# motor_board_tmc.net
KiCad netlist of a schematic drawn in EAGLE
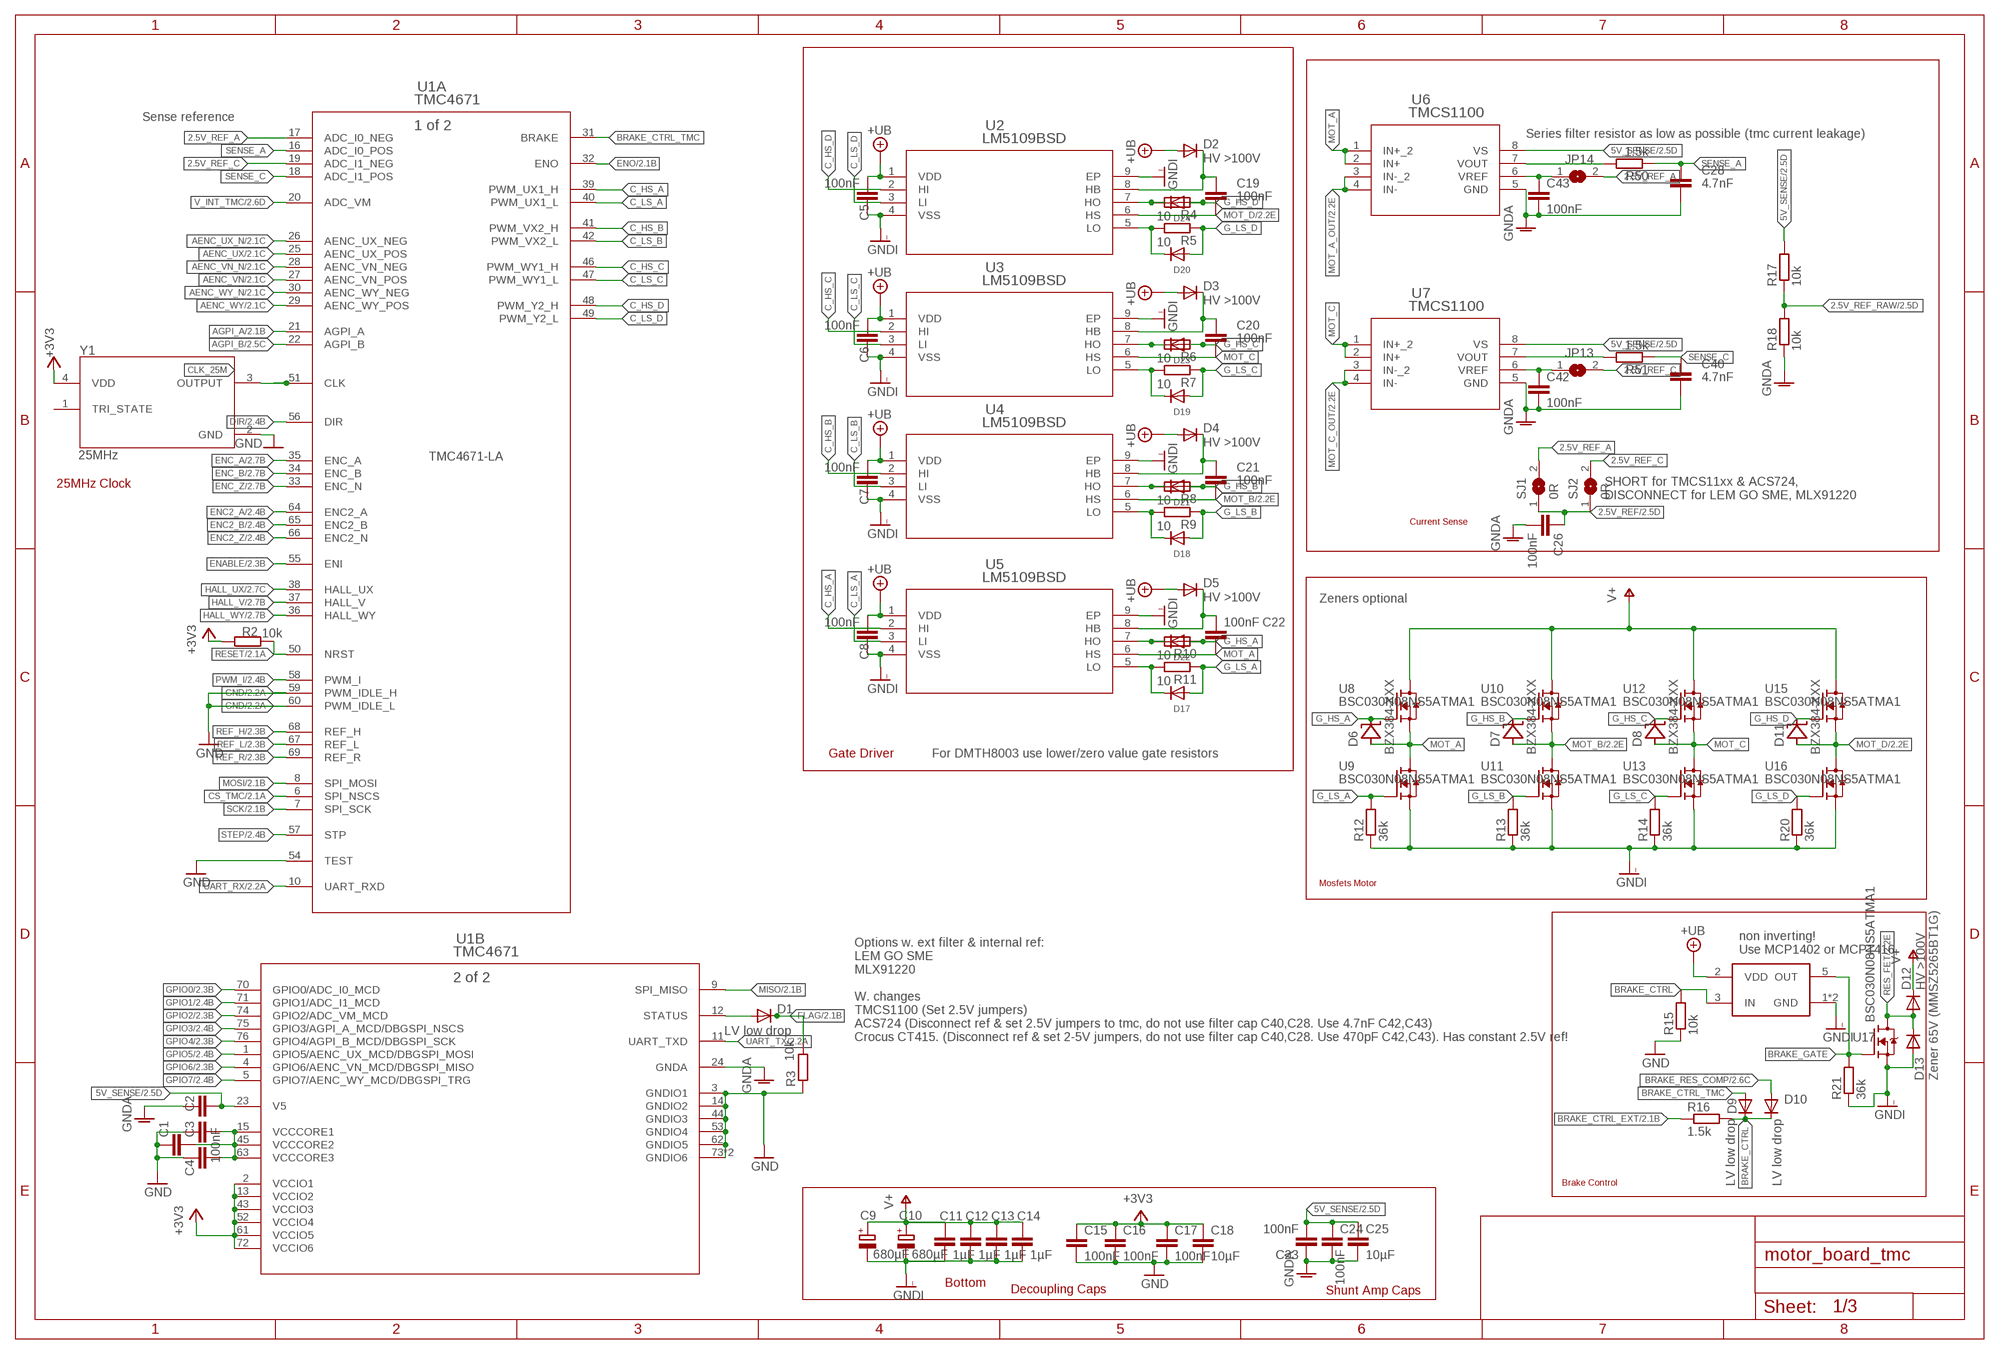
[diagram p0: schematic, sheet 1]
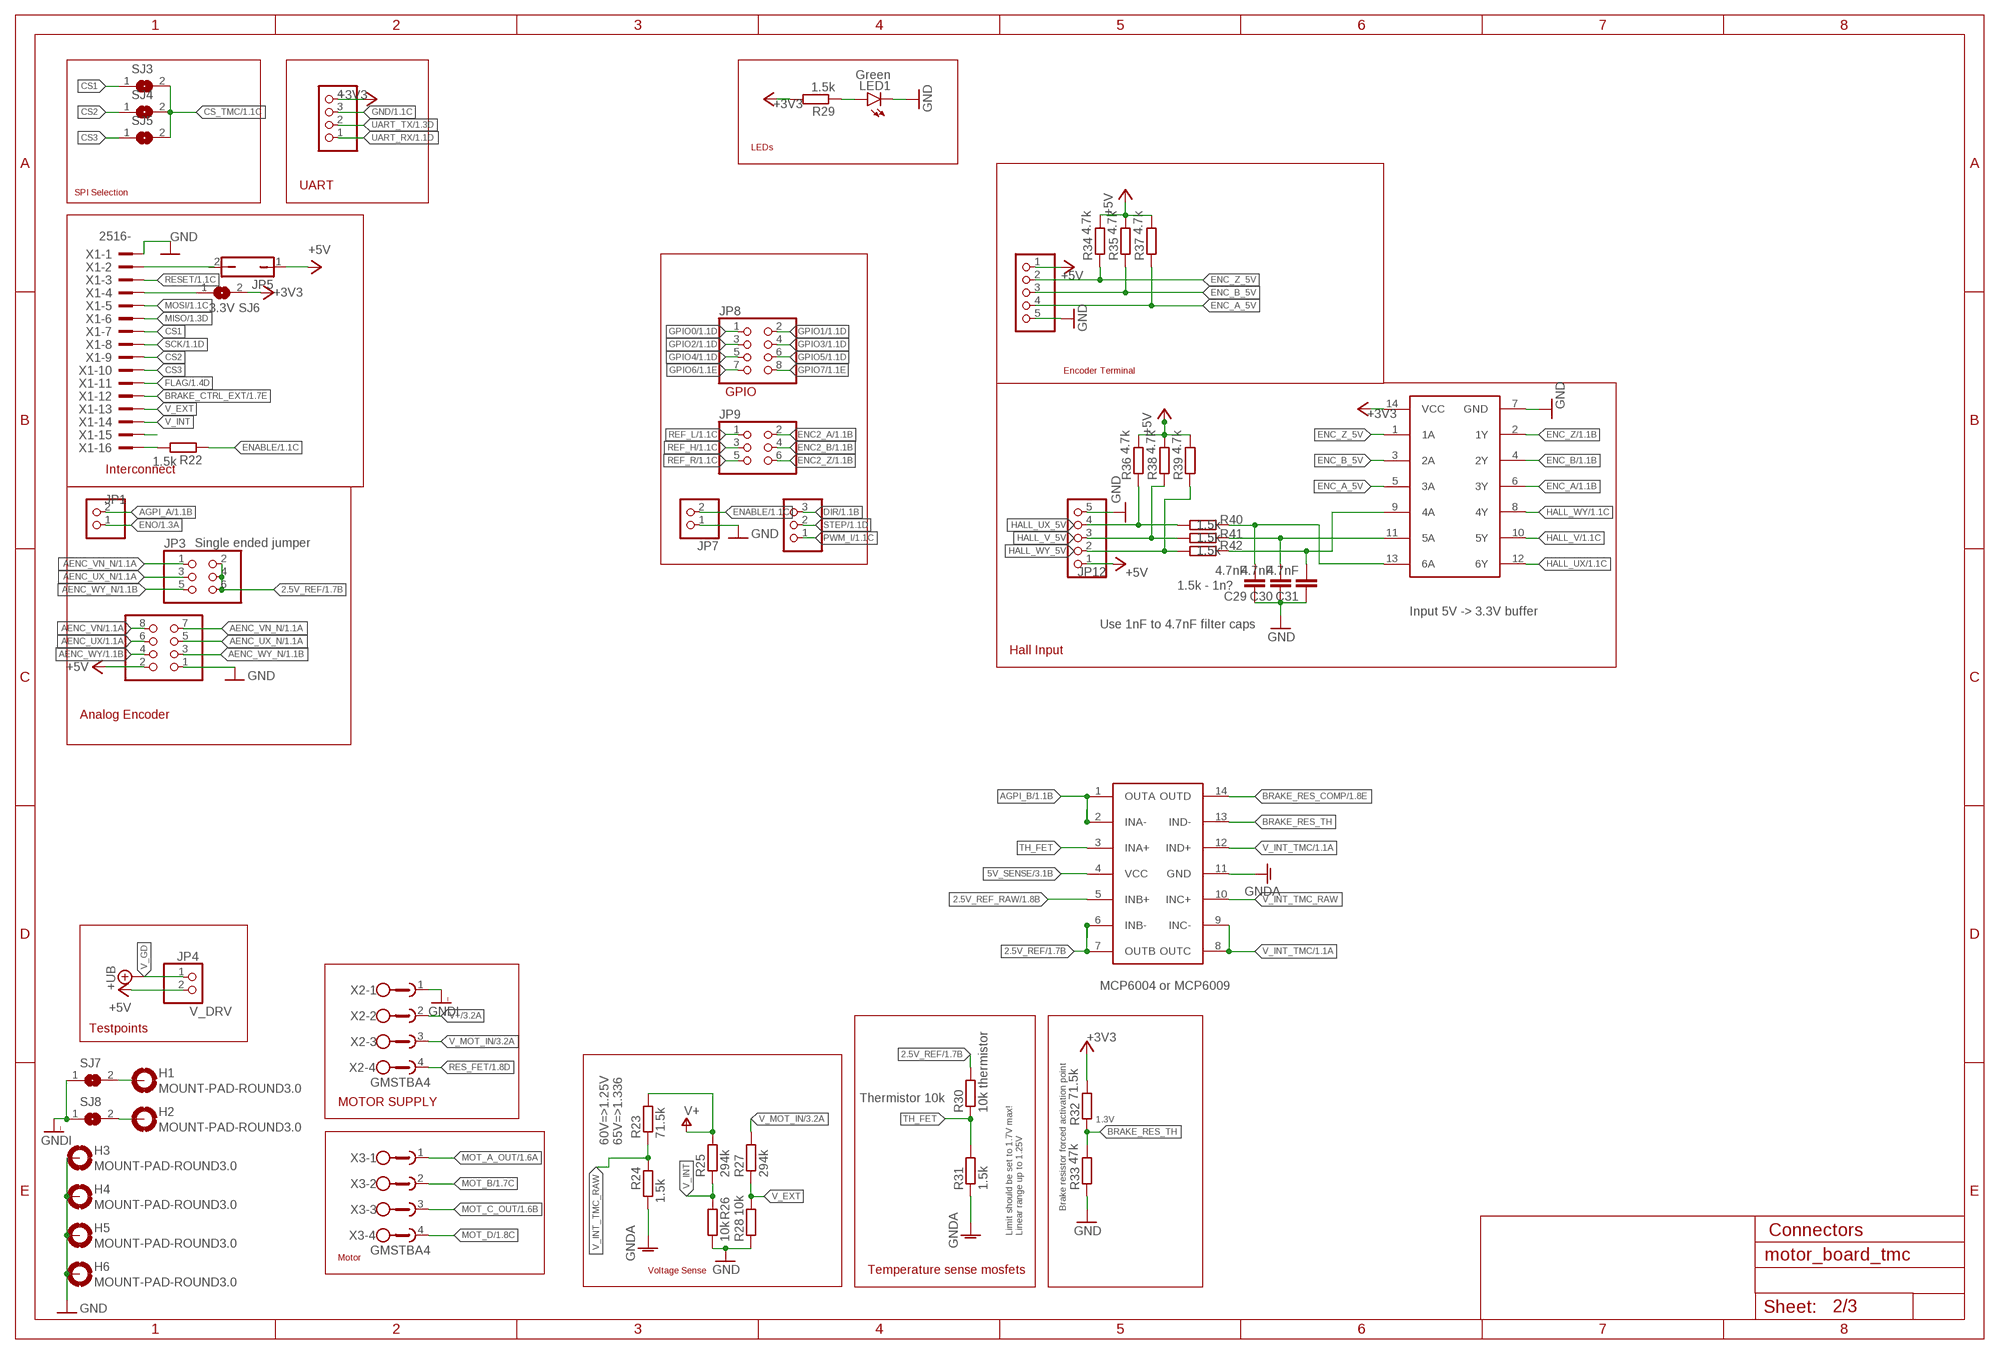
[diagram p1: schematic, sheet 2]
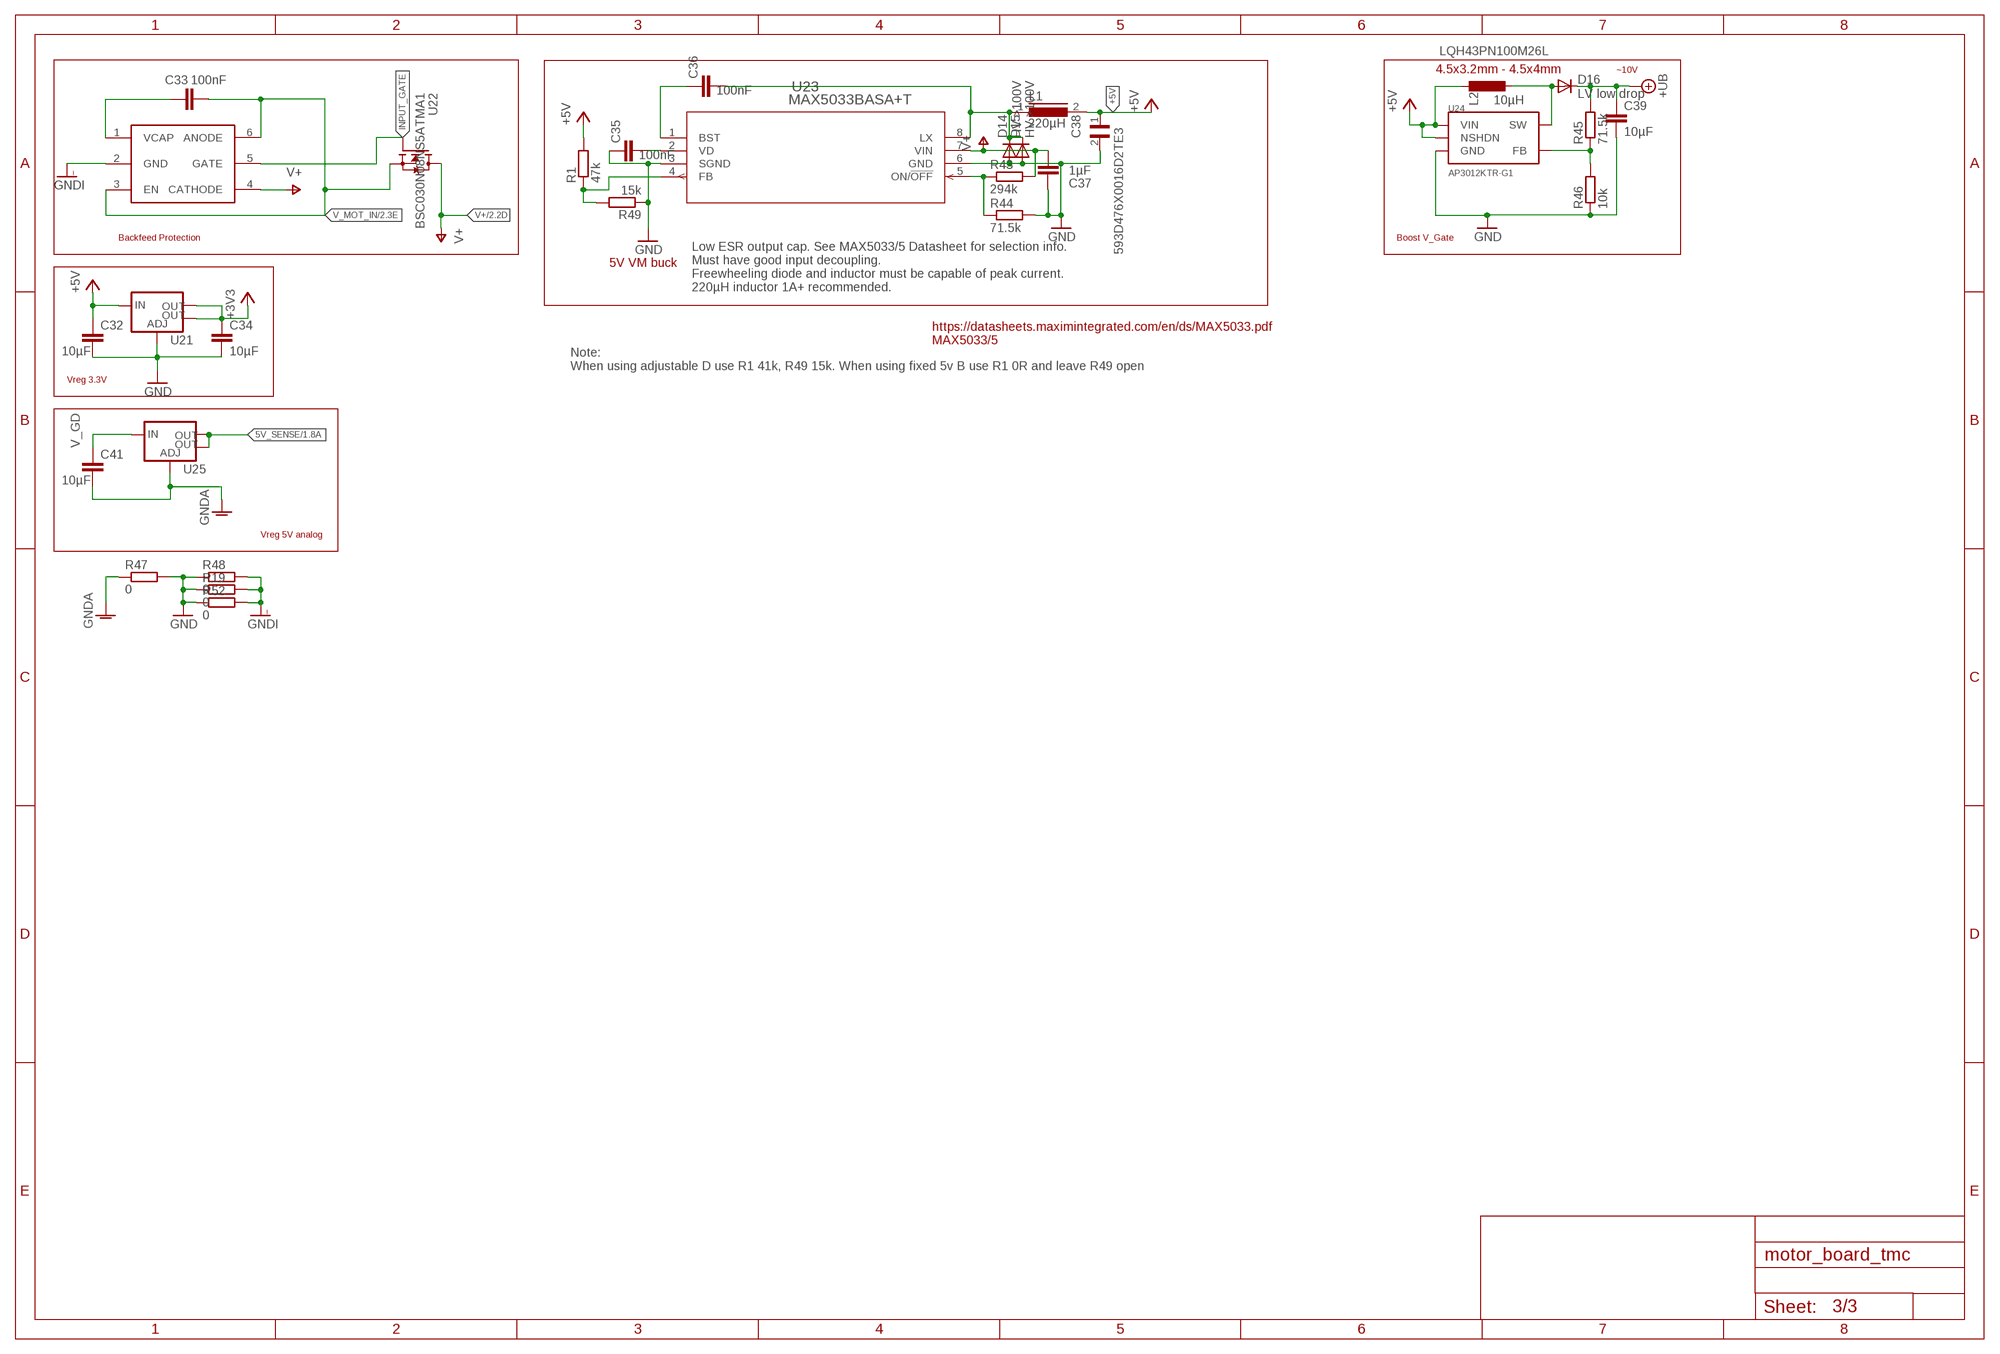
[diagram p2: schematic, sheet 3]

(export (version "E")
  (design (tool "Eeschema 10.0.6"))
  (components
    (comp (ref "C32")
      (value "10µF")
      (footprint "eagle-import:C0805")
      (libsource (lib "eagle-import") (part "C-EUC0805"))
    )
    (comp (ref "C33")
      (value "100nF")
      (footprint "eagle-import:C0603")
      (libsource (lib "eagle-import") (part "C-EUC0603"))
    )
    (comp (ref "C34")
      (value "10µF")
      (footprint "eagle-import:C0805")
      (libsource (lib "eagle-import") (part "C-EUC0805"))
    )
    (comp (ref "C35")
      (value "100nF")
      (footprint "eagle-import:C0603")
      (libsource (lib "eagle-import") (part "C-EUC0603"))
    )
    (comp (ref "C36")
      (value "100nF")
      (footprint "eagle-import:C0603")
      (libsource (lib "eagle-import") (part "C-EUC0603"))
    )
    (comp (ref "C37")
      (value "1µF")
      (footprint "eagle-import:C1206")
      (libsource (lib "eagle-import") (part "C-EUC1206"))
    )
    (comp (ref "C38")
      (value "593D476X0016D2TE3")
      (footprint "eagle-import:CAPPM7343X310N")
      (fields (field (name "DIGI-KEY_PART_NUMBER") "718-2142-1-ND") (field (name "MF") "Vishay Sprague"))
      (libsource (lib "eagle-import") (part "593D476X0016D2TE3"))
    )
    (comp (ref "C39")
      (value "10µF")
      (footprint "eagle-import:C0805")
      (libsource (lib "eagle-import") (part "C-EUC0805"))
    )
    (comp (ref "C41")
      (value "10µF")
      (footprint "eagle-import:C0805")
      (libsource (lib "eagle-import") (part "C-EUC0805"))
    )
    (comp (ref "D14")
      (value "HV >100V")
      (footprint "eagle-import:SOD-123FL")
      (libsource (lib "eagle-import") (part "DIODE_SOD-123FL"))
    )
    (comp (ref "D15")
      (value "HV >100V")
      (footprint "eagle-import:SMADIODE")
      (libsource (lib "eagle-import") (part "DIODESMA"))
    )
    (comp (ref "D16")
      (value "LV low drop")
      (footprint "eagle-import:SOD-123FL")
      (libsource (lib "eagle-import") (part "DIODE_SOD-123FL"))
    )
    (comp (ref "L1")
      (value "220µH")
      (footprint "eagle-import:8MMINDUCTOR")
      (libsource (lib "eagle-import") (part "8MMINDUCTOR"))
    )
    (comp (ref "L2")
      (value "10µH")
      (footprint "eagle-import:L4532P")
      (libsource (lib "eagle-import") (part "L-EUL4532P"))
    )
    (comp (ref "R1")
      (value "47k")
      (footprint "eagle-import:R0603")
      (libsource (lib "eagle-import") (part "R-EU_R0603"))
    )
    (comp (ref "R19")
      (value "0")
      (footprint "eagle-import:R0603")
      (libsource (lib "eagle-import") (part "R-EU_R0603"))
    )
    (comp (ref "R43")
      (value "294k")
      (footprint "eagle-import:R0805")
      (libsource (lib "eagle-import") (part "R-EU_R0805"))
    )
    (comp (ref "R44")
      (value "71.5k")
      (footprint "eagle-import:R0805")
      (libsource (lib "eagle-import") (part "R-EU_R0805"))
    )
    (comp (ref "R45")
      (value "71.5k")
      (footprint "eagle-import:R0805")
      (libsource (lib "eagle-import") (part "R-EU_R0805"))
    )
    (comp (ref "R46")
      (value "10k")
      (footprint "eagle-import:R0603")
      (libsource (lib "eagle-import") (part "R-EU_R0603"))
    )
    (comp (ref "R47")
      (value "0")
      (footprint "eagle-import:R0603")
      (libsource (lib "eagle-import") (part "R-EU_R0603"))
    )
    (comp (ref "R48")
      (value "0")
      (footprint "eagle-import:R0603")
      (libsource (lib "eagle-import") (part "R-EU_R0603"))
    )
    (comp (ref "R49")
      (value "15k")
      (footprint "eagle-import:R0603")
      (libsource (lib "eagle-import") (part "R-EU_R0603"))
    )
    (comp (ref "R52")
      (value "0")
      (footprint "eagle-import:R0603")
      (libsource (lib "eagle-import") (part "R-EU_R0603"))
    )
    (comp (ref "U20")
      (value "LM74700-Q1")
      (footprint "eagle-import:SOT23-6")
      (libsource (lib "eagle-import") (part "LM74700-Q1"))
    )
    (comp (ref "U21")
      (value "V_REG_LM1117SOT223")
      (footprint "eagle-import:SOT223")
      (libsource (lib "eagle-import") (part "V_REG_LM1117SOT223"))
    )
    (comp (ref "U22")
      (value "BSC030N08NS5ATMA1")
      (footprint "eagle-import:MOSFET_BSC093N04LSGATMA1")
      (fields (field (name "MF") "Infineon Technologies"))
      (libsource (lib "eagle-import") (part "BSC030N08NS5ATMA1"))
    )
    (comp (ref "U23")
      (value "MAX5033BASA+T")
      (footprint "eagle-import:21-0041B_8_MXM")
      (fields (field (name "MANUFACTURER_PART_NUMBER") "max5033basa+T"))
      (libsource (lib "eagle-import") (part "MAX5033BASA+T"))
    )
    (comp (ref "U24")
      (value "AP3012KTR-G1")
      (footprint "eagle-import:SOT23-5L")
      (libsource (lib "eagle-import") (part "AP3012KTR-G1"))
    )
    (comp (ref "U25")
      (value "V_REG_LM1117SOT223")
      (footprint "eagle-import:SOT223")
      (libsource (lib "eagle-import") (part "V_REG_LM1117SOT223"))
    )
    (comp (ref "C29")
      (value "4.7nF")
      (footprint "eagle-import:C0603")
      (libsource (lib "eagle-import") (part "C-EUC0603"))
    )
    (comp (ref "C30")
      (value "4.7nF")
      (footprint "eagle-import:C0603")
      (libsource (lib "eagle-import") (part "C-EUC0603"))
    )
    (comp (ref "C31")
      (value "4.7nF")
      (footprint "eagle-import:C0603")
      (libsource (lib "eagle-import") (part "C-EUC0603"))
    )
    (comp (ref "H1")
      (value "MOUNT-PAD-ROUND3.0")
      (footprint "eagle-import:3,0-PAD")
      (libsource (lib "eagle-import") (part "MOUNT-PAD-ROUND3.0"))
    )
    (comp (ref "H2")
      (value "MOUNT-PAD-ROUND3.0")
      (footprint "eagle-import:3,0-PAD")
      (libsource (lib "eagle-import") (part "MOUNT-PAD-ROUND3.0"))
    )
    (comp (ref "H3")
      (value "MOUNT-PAD-ROUND3.0")
      (footprint "eagle-import:3,0-PAD")
      (libsource (lib "eagle-import") (part "MOUNT-PAD-ROUND3.0"))
    )
    (comp (ref "H4")
      (value "MOUNT-PAD-ROUND3.0")
      (footprint "eagle-import:3,0-PAD")
      (libsource (lib "eagle-import") (part "MOUNT-PAD-ROUND3.0"))
    )
    (comp (ref "H5")
      (value "MOUNT-PAD-ROUND3.0")
      (footprint "eagle-import:3,0-PAD")
      (libsource (lib "eagle-import") (part "MOUNT-PAD-ROUND3.0"))
    )
    (comp (ref "H6")
      (value "MOUNT-PAD-ROUND3.0")
      (footprint "eagle-import:3,0-PAD")
      (libsource (lib "eagle-import") (part "MOUNT-PAD-ROUND3.0"))
    )
    (comp (ref "JP1")
      (value "PINHD-1X2")
      (footprint "eagle-import:1X02")
      (libsource (lib "eagle-import") (part "PINHD-1X2"))
    )
    (comp (ref "JP2")
      (value "PINHD-2X4")
      (footprint "eagle-import:2X04")
      (libsource (lib "eagle-import") (part "PINHD-2X4"))
    )
    (comp (ref "JP3")
      (value "PINHD-2X3")
      (footprint "eagle-import:2X03")
      (libsource (lib "eagle-import") (part "PINHD-2X3"))
    )
    (comp (ref "JP4")
      (value "V_DRV")
      (footprint "eagle-import:1X02")
      (libsource (lib "eagle-import") (part "PINHD-1X2"))
    )
    (comp (ref "JP5")
      (value "JP1Q")
      (footprint "eagle-import:JP1")
      (libsource (lib "eagle-import") (part "JP1Q"))
    )
    (comp (ref "JP6")
      (value "PINHD-1X4")
      (footprint "eagle-import:1X04")
      (libsource (lib "eagle-import") (part "PINHD-1X4"))
    )
    (comp (ref "JP7")
      (value "PINHD-1X2")
      (footprint "eagle-import:1X02")
      (libsource (lib "eagle-import") (part "PINHD-1X2"))
    )
    (comp (ref "JP8")
      (value "PINHD-2X4")
      (footprint "eagle-import:2X04")
      (libsource (lib "eagle-import") (part "PINHD-2X4"))
    )
    (comp (ref "JP9")
      (value "PINHD-2X3")
      (footprint "eagle-import:2X03")
      (libsource (lib "eagle-import") (part "PINHD-2X3"))
    )
    (comp (ref "JP10")
      (value "PINHD-1X3")
      (footprint "eagle-import:1X03")
      (libsource (lib "eagle-import") (part "PINHD-1X3"))
    )
    (comp (ref "JP11")
      (value "PINHD-1X5")
      (footprint "eagle-import:1X05")
      (libsource (lib "eagle-import") (part "PINHD-1X5"))
    )
    (comp (ref "JP12")
      (value "PINHD-1X5")
      (footprint "eagle-import:1X05")
      (libsource (lib "eagle-import") (part "PINHD-1X5"))
    )
    (comp (ref "LED1")
      (value "Green")
      (footprint "eagle-import:SML0805")
      (libsource (lib "eagle-import") (part "LEDSML0805"))
    )
    (comp (ref "R22")
      (value "1.5k")
      (footprint "eagle-import:R0603")
      (libsource (lib "eagle-import") (part "R-EU_R0603"))
    )
    (comp (ref "R23")
      (value "71.5k")
      (footprint "eagle-import:R0805")
      (libsource (lib "eagle-import") (part "R-EU_R0805"))
    )
    (comp (ref "R24")
      (value "1.5k")
      (footprint "eagle-import:R0603")
      (libsource (lib "eagle-import") (part "R-EU_R0603"))
    )
    (comp (ref "R25")
      (value "294k")
      (footprint "eagle-import:R0805")
      (libsource (lib "eagle-import") (part "R-EU_R0805"))
    )
    (comp (ref "R26")
      (value "10k")
      (footprint "eagle-import:R0603")
      (libsource (lib "eagle-import") (part "R-EU_R0603"))
    )
    (comp (ref "R27")
      (value "294k")
      (footprint "eagle-import:R0805")
      (libsource (lib "eagle-import") (part "R-EU_R0805"))
    )
    (comp (ref "R28")
      (value "10k")
      (footprint "eagle-import:R0603")
      (libsource (lib "eagle-import") (part "R-EU_R0603"))
    )
    (comp (ref "R29")
      (value "1.5k")
      (footprint "eagle-import:R0603")
      (libsource (lib "eagle-import") (part "R-EU_R0603"))
    )
    (comp (ref "R30")
      (value "10k thermistor")
      (footprint "eagle-import:R0603")
      (libsource (lib "eagle-import") (part "R-EU_R0603"))
    )
    (comp (ref "R31")
      (value "1.5k")
      (footprint "eagle-import:R0603")
      (libsource (lib "eagle-import") (part "R-EU_R0603"))
    )
    (comp (ref "R32")
      (value "71.5k")
      (footprint "eagle-import:R0805")
      (libsource (lib "eagle-import") (part "R-EU_R0805"))
    )
    (comp (ref "R33")
      (value "47k")
      (footprint "eagle-import:R0603")
      (libsource (lib "eagle-import") (part "R-EU_R0603"))
    )
    (comp (ref "R34")
      (value "4.7k")
      (footprint "eagle-import:R0603")
      (libsource (lib "eagle-import") (part "R-EU_R0603"))
    )
    (comp (ref "R35")
      (value "4.7k")
      (footprint "eagle-import:R0603")
      (libsource (lib "eagle-import") (part "R-EU_R0603"))
    )
    (comp (ref "R36")
      (value "4.7k")
      (footprint "eagle-import:R0603")
      (libsource (lib "eagle-import") (part "R-EU_R0603"))
    )
    (comp (ref "R37")
      (value "4.7k")
      (footprint "eagle-import:R0603")
      (libsource (lib "eagle-import") (part "R-EU_R0603"))
    )
    (comp (ref "R38")
      (value "4.7k")
      (footprint "eagle-import:R0603")
      (libsource (lib "eagle-import") (part "R-EU_R0603"))
    )
    (comp (ref "R39")
      (value "4.7k")
      (footprint "eagle-import:R0603")
      (libsource (lib "eagle-import") (part "R-EU_R0603"))
    )
    (comp (ref "R40")
      (value "1.5k")
      (footprint "eagle-import:R0603")
      (libsource (lib "eagle-import") (part "R-EU_R0603"))
    )
    (comp (ref "R41")
      (value "1.5k")
      (footprint "eagle-import:R0603")
      (libsource (lib "eagle-import") (part "R-EU_R0603"))
    )
    (comp (ref "R42")
      (value "1.5k")
      (footprint "eagle-import:R0603")
      (libsource (lib "eagle-import") (part "R-EU_R0603"))
    )
    (comp (ref "SJ3") (value "SJ") (footprint "eagle-import:SJ") (libsource (lib "eagle-import") (part "SJ")))
    (comp (ref "SJ4") (value "SJ") (footprint "eagle-import:SJ") (libsource (lib "eagle-import") (part "SJ")))
    (comp (ref "SJ5") (value "SJ") (footprint "eagle-import:SJ") (libsource (lib "eagle-import") (part "SJ")))
    (comp (ref "SJ6")
      (value "3.3V")
      (footprint "eagle-import:SJ")
      (libsource (lib "eagle-import") (part "SJ"))
    )
    (comp (ref "SJ7") (value "SJ") (footprint "eagle-import:SJ") (libsource (lib "eagle-import") (part "SJ")))
    (comp (ref "SJ8") (value "SJ") (footprint "eagle-import:SJ") (libsource (lib "eagle-import") (part "SJ")))
    (comp (ref "U18")
      (value "MCP6004")
      (footprint "eagle-import:TSSOP14")
      (libsource (lib "eagle-import") (part "MCP6004"))
    )
    (comp (ref "U19")
      (value "74LV17APWJ")
      (footprint "eagle-import:TSSOP14")
      (libsource (lib "eagle-import") (part "74LV17APWJ"))
    )
    (comp (ref "X1")
      (value "2516-")
      (footprint "eagle-import:PAK100_2500-16")
      (libsource (lib "eagle-import") (part "2516-"))
    )
    (comp (ref "X2")
      (value "GMSTBA4")
      (footprint "eagle-import:GMSTBA4")
      (fields (field (name "MF") "FARNELL") (field (name "MPN") "1757268"))
      (libsource (lib "eagle-import") (part "GMSTBA4"))
    )
    (comp (ref "X3")
      (value "GMSTBA4")
      (footprint "eagle-import:GMSTBA4")
      (fields (field (name "MF") "FARNELL") (field (name "MPN") "1757268"))
      (libsource (lib "eagle-import") (part "GMSTBA4"))
    )
    (comp (ref "C1")
      (value "100nF")
      (footprint "eagle-import:C0603")
      (libsource (lib "eagle-import") (part "C-EUC0603"))
    )
    (comp (ref "C2")
      (value "10µF")
      (footprint "eagle-import:C0805")
      (libsource (lib "eagle-import") (part "C-EUC0805"))
    )
    (comp (ref "C3")
      (value "100nF")
      (footprint "eagle-import:C0603")
      (libsource (lib "eagle-import") (part "C-EUC0603"))
    )
    (comp (ref "C4")
      (value "100nF")
      (footprint "eagle-import:C0603")
      (libsource (lib "eagle-import") (part "C-EUC0603"))
    )
    (comp (ref "C5")
      (value "100nF")
      (footprint "eagle-import:C0603")
      (libsource (lib "eagle-import") (part "C-EUC0603"))
    )
    (comp (ref "C6")
      (value "100nF")
      (footprint "eagle-import:C0603")
      (libsource (lib "eagle-import") (part "C-EUC0603"))
    )
    (comp (ref "C7")
      (value "100nF")
      (footprint "eagle-import:C0603")
      (libsource (lib "eagle-import") (part "C-EUC0603"))
    )
    (comp (ref "C8")
      (value "100nF")
      (footprint "eagle-import:C0603")
      (libsource (lib "eagle-import") (part "C-EUC0603"))
    )
    (comp (ref "C9")
      (value "680µF")
      (footprint "eagle-import:E7,5-16")
      (libsource (lib "eagle-import") (part "CPOL-EUE7.5-16"))
    )
    (comp (ref "C10")
      (value "680µF")
      (footprint "eagle-import:E7,5-16")
      (libsource (lib "eagle-import") (part "CPOL-EUE7.5-16"))
    )
    (comp (ref "C11")
      (value "1µF")
      (footprint "eagle-import:C1206")
      (libsource (lib "eagle-import") (part "C-EUC1206"))
    )
    (comp (ref "C12")
      (value "1µF")
      (footprint "eagle-import:C1206")
      (libsource (lib "eagle-import") (part "C-EUC1206"))
    )
    (comp (ref "C13")
      (value "1µF")
      (footprint "eagle-import:C1206")
      (libsource (lib "eagle-import") (part "C-EUC1206"))
    )
    (comp (ref "C14")
      (value "1µF")
      (footprint "eagle-import:C1206")
      (libsource (lib "eagle-import") (part "C-EUC1206"))
    )
    (comp (ref "C15")
      (value "100nF")
      (footprint "eagle-import:C0603")
      (libsource (lib "eagle-import") (part "C-EUC0603"))
    )
    (comp (ref "C16")
      (value "100nF")
      (footprint "eagle-import:C0603")
      (libsource (lib "eagle-import") (part "C-EUC0603"))
    )
    (comp (ref "C17")
      (value "100nF")
      (footprint "eagle-import:C0603")
      (libsource (lib "eagle-import") (part "C-EUC0603"))
    )
    (comp (ref "C18")
      (value "10µF")
      (footprint "eagle-import:C0805")
      (libsource (lib "eagle-import") (part "C-EUC0805"))
    )
    (comp (ref "C19")
      (value "100nF")
      (footprint "eagle-import:C0603")
      (libsource (lib "eagle-import") (part "C-EUC0603"))
    )
    (comp (ref "C20")
      (value "100nF")
      (footprint "eagle-import:C0603")
      (libsource (lib "eagle-import") (part "C-EUC0603"))
    )
    (comp (ref "C21")
      (value "100nF")
      (footprint "eagle-import:C0603")
      (libsource (lib "eagle-import") (part "C-EUC0603"))
    )
    (comp (ref "C22")
      (value "100nF")
      (footprint "eagle-import:C0603")
      (libsource (lib "eagle-import") (part "C-EUC0603"))
    )
    (comp (ref "C23")
      (value "100nF")
      (footprint "eagle-import:C0603")
      (libsource (lib "eagle-import") (part "C-EUC0603"))
    )
    (comp (ref "C24")
      (value "100nF")
      (footprint "eagle-import:C0603")
      (libsource (lib "eagle-import") (part "C-EUC0603"))
    )
    (comp (ref "C25")
      (value "10µF")
      (footprint "eagle-import:C0805")
      (libsource (lib "eagle-import") (part "C-EUC0805"))
    )
    (comp (ref "C26")
      (value "100nF")
      (footprint "eagle-import:C0603")
      (libsource (lib "eagle-import") (part "C-EUC0603"))
    )
    (comp (ref "C28")
      (value "4.7nF")
      (footprint "eagle-import:C0603")
      (libsource (lib "eagle-import") (part "C-EUC0603"))
    )
    (comp (ref "C40")
      (value "4.7nF")
      (footprint "eagle-import:C0603")
      (libsource (lib "eagle-import") (part "C-EUC0603"))
    )
    (comp (ref "C42")
      (value "100nF")
      (footprint "eagle-import:C0603")
      (libsource (lib "eagle-import") (part "C-EUC0603"))
    )
    (comp (ref "C43")
      (value "100nF")
      (footprint "eagle-import:C0603")
      (libsource (lib "eagle-import") (part "C-EUC0603"))
    )
    (comp (ref "D1")
      (value "LV low drop")
      (footprint "eagle-import:SOD-123FL")
      (libsource (lib "eagle-import") (part "DIODE_SOD-123FL"))
    )
    (comp (ref "D2")
      (value "HV >100V")
      (footprint "eagle-import:SOD-123FL")
      (libsource (lib "eagle-import") (part "DIODE_SOD-123FL"))
    )
    (comp (ref "D3")
      (value "HV >100V")
      (footprint "eagle-import:SOD-123FL")
      (libsource (lib "eagle-import") (part "DIODE_SOD-123FL"))
    )
    (comp (ref "D4")
      (value "HV >100V")
      (footprint "eagle-import:SOD-123FL")
      (libsource (lib "eagle-import") (part "DIODE_SOD-123FL"))
    )
    (comp (ref "D5")
      (value "HV >100V")
      (footprint "eagle-import:SOD-123FL")
      (libsource (lib "eagle-import") (part "DIODE_SOD-123FL"))
    )
    (comp (ref "D6")
      (value "BZX384-XXX")
      (footprint "eagle-import:SOD323-R")
      (libsource (lib "eagle-import") (part "BZX384-XXX"))
    )
    (comp (ref "D7")
      (value "BZX384-XXX")
      (footprint "eagle-import:SOD323-R")
      (libsource (lib "eagle-import") (part "BZX384-XXX"))
    )
    (comp (ref "D8")
      (value "BZX384-XXX")
      (footprint "eagle-import:SOD323-R")
      (libsource (lib "eagle-import") (part "BZX384-XXX"))
    )
    (comp (ref "D9")
      (value "LV low drop")
      (footprint "eagle-import:SOD-123FL")
      (libsource (lib "eagle-import") (part "DIODE_SOD-123FL"))
    )
    (comp (ref "D10")
      (value "LV low drop")
      (footprint "eagle-import:SOD-123FL")
      (libsource (lib "eagle-import") (part "DIODE_SOD-123FL"))
    )
    (comp (ref "D11")
      (value "BZX384-XXX")
      (footprint "eagle-import:SOD323-R")
      (libsource (lib "eagle-import") (part "BZX384-XXX"))
    )
    (comp (ref "D12")
      (value "HV >100V")
      (footprint "eagle-import:SOD-123FL")
      (libsource (lib "eagle-import") (part "DIODE_SOD-123FL"))
    )
    (comp (ref "D13")
      (value "Zener 65V (MMSZ5265BT1G)")
      (footprint "eagle-import:SOD-123FL")
      (libsource (lib "eagle-import") (part "DIODE_SOD-123FL"))
    )
    (comp (ref "D17")
      (value "DIODESOD-323F")
      (footprint "eagle-import:SOD-323F")
      (libsource (lib "eagle-import") (part "DIODESOD-323F"))
    )
    (comp (ref "D18")
      (value "DIODESOD-323F")
      (footprint "eagle-import:SOD-323F")
      (libsource (lib "eagle-import") (part "DIODESOD-323F"))
    )
    (comp (ref "D19")
      (value "DIODESOD-323F")
      (footprint "eagle-import:SOD-323F")
      (libsource (lib "eagle-import") (part "DIODESOD-323F"))
    )
    (comp (ref "D20")
      (value "DIODESOD-323F")
      (footprint "eagle-import:SOD-323F")
      (libsource (lib "eagle-import") (part "DIODESOD-323F"))
    )
    (comp (ref "D21")
      (value "DIODESOD-323F")
      (footprint "eagle-import:SOD-323F")
      (libsource (lib "eagle-import") (part "DIODESOD-323F"))
    )
    (comp (ref "D22")
      (value "DIODESOD-323F")
      (footprint "eagle-import:SOD-323F")
      (libsource (lib "eagle-import") (part "DIODESOD-323F"))
    )
    (comp (ref "D23")
      (value "DIODESOD-323F")
      (footprint "eagle-import:SOD-323F")
      (libsource (lib "eagle-import") (part "DIODESOD-323F"))
    )
    (comp (ref "D24")
      (value "DIODESOD-323F")
      (footprint "eagle-import:SOD-323F")
      (libsource (lib "eagle-import") (part "DIODESOD-323F"))
    )
    (comp (ref "JP13")
      (value "JUMPER-SMT_2_NO_SILK")
      (footprint "eagle-import:RESISTOR_R0603")
      (libsource (lib "eagle-import") (part "RESJUMPER0603"))
    )
    (comp (ref "JP14")
      (value "JUMPER-SMT_2_NO_SILK")
      (footprint "eagle-import:RESISTOR_R0603")
      (libsource (lib "eagle-import") (part "RESJUMPER0603"))
    )
    (comp (ref "R2")
      (value "10k")
      (footprint "eagle-import:R0603")
      (libsource (lib "eagle-import") (part "R-EU_R0603"))
    )
    (comp (ref "R3")
      (value "10k")
      (footprint "eagle-import:R0603")
      (libsource (lib "eagle-import") (part "R-EU_R0603"))
    )
    (comp (ref "R4")
      (value "10")
      (footprint "eagle-import:R0603")
      (libsource (lib "eagle-import") (part "R-EU_R0603"))
    )
    (comp (ref "R5")
      (value "10")
      (footprint "eagle-import:R0603")
      (libsource (lib "eagle-import") (part "R-EU_R0603"))
    )
    (comp (ref "R6")
      (value "10")
      (footprint "eagle-import:R0603")
      (libsource (lib "eagle-import") (part "R-EU_R0603"))
    )
    (comp (ref "R7")
      (value "10")
      (footprint "eagle-import:R0603")
      (libsource (lib "eagle-import") (part "R-EU_R0603"))
    )
    (comp (ref "R8")
      (value "10")
      (footprint "eagle-import:R0603")
      (libsource (lib "eagle-import") (part "R-EU_R0603"))
    )
    (comp (ref "R9")
      (value "10")
      (footprint "eagle-import:R0603")
      (libsource (lib "eagle-import") (part "R-EU_R0603"))
    )
    (comp (ref "R10")
      (value "10")
      (footprint "eagle-import:R0603")
      (libsource (lib "eagle-import") (part "R-EU_R0603"))
    )
    (comp (ref "R11")
      (value "10")
      (footprint "eagle-import:R0603")
      (libsource (lib "eagle-import") (part "R-EU_R0603"))
    )
    (comp (ref "R12")
      (value "36k")
      (footprint "eagle-import:R0603")
      (libsource (lib "eagle-import") (part "R-EU_R0603"))
    )
    (comp (ref "R13")
      (value "36k")
      (footprint "eagle-import:R0603")
      (libsource (lib "eagle-import") (part "R-EU_R0603"))
    )
    (comp (ref "R14")
      (value "36k")
      (footprint "eagle-import:R0603")
      (libsource (lib "eagle-import") (part "R-EU_R0603"))
    )
    (comp (ref "R15")
      (value "10k")
      (footprint "eagle-import:R0603")
      (libsource (lib "eagle-import") (part "R-EU_R0603"))
    )
    (comp (ref "R16")
      (value "1.5k")
      (footprint "eagle-import:R0603")
      (libsource (lib "eagle-import") (part "R-EU_R0603"))
    )
    (comp (ref "R17")
      (value "10k")
      (footprint "eagle-import:R0603")
      (libsource (lib "eagle-import") (part "R-EU_R0603"))
    )
    (comp (ref "R18")
      (value "10k")
      (footprint "eagle-import:R0603")
      (libsource (lib "eagle-import") (part "R-EU_R0603"))
    )
    (comp (ref "R20")
      (value "36k")
      (footprint "eagle-import:R0603")
      (libsource (lib "eagle-import") (part "R-EU_R0603"))
    )
    (comp (ref "R21")
      (value "36k")
      (footprint "eagle-import:R0603")
      (libsource (lib "eagle-import") (part "R-EU_R0603"))
    )
    (comp (ref "R50")
      (value "1.5k")
      (footprint "eagle-import:R0603")
      (libsource (lib "eagle-import") (part "R-EU_R0603"))
    )
    (comp (ref "R51")
      (value "1.5k")
      (footprint "eagle-import:R0603")
      (libsource (lib "eagle-import") (part "R-EU_R0603"))
    )
    (comp (ref "SJ1")
      (value "0R")
      (footprint "eagle-import:RESISTOR_R0603")
      (libsource (lib "eagle-import") (part "RESJUMPER0603"))
    )
    (comp (ref "SJ2")
      (value "0R")
      (footprint "eagle-import:RESISTOR_R0603")
      (libsource (lib "eagle-import") (part "RESJUMPER0603"))
    )
    (comp (ref "U1")
      (value "TMC4671")
      (footprint "eagle-import:QFN76_10P5X6P5")
      (fields (field (name "MANUFACTURER_PART_NUMBER") "TMC4671ES"))
      (libsource (lib "eagle-import") (part "TMC4671"))
    )
    (comp (ref "U2")
      (value "LM5109BSD")
      (footprint "eagle-import:SDC08A")
      (fields (field (name "MANUFACTURER_PART_NUMBER") "lm5109bsd"))
      (libsource (lib "eagle-import") (part "LM5109BSD"))
    )
    (comp (ref "U3")
      (value "LM5109BSD")
      (footprint "eagle-import:SDC08A")
      (fields (field (name "MANUFACTURER_PART_NUMBER") "lm5109bsd"))
      (libsource (lib "eagle-import") (part "LM5109BSD"))
    )
    (comp (ref "U4")
      (value "LM5109BSD")
      (footprint "eagle-import:SDC08A")
      (fields (field (name "MANUFACTURER_PART_NUMBER") "lm5109bsd"))
      (libsource (lib "eagle-import") (part "LM5109BSD"))
    )
    (comp (ref "U5")
      (value "LM5109BSD")
      (footprint "eagle-import:SDC08A")
      (fields (field (name "MANUFACTURER_PART_NUMBER") "lm5109bsd"))
      (libsource (lib "eagle-import") (part "LM5109BSD"))
    )
    (comp (ref "U6")
      (value "TMCS1100")
      (footprint "eagle-import:SOIC8_D_TEX")
      (fields
        (field (name "MANUFACTURER_PART_NUMBER") "TMCS1100AxQDR")
        (field (name "COPYRIGHT") "Copyright (C) 2018 Accelerated Designs. All rights reserved")
      )
      (libsource (lib "eagle-import") (part "TMCS1100"))
    )
    (comp (ref "U7")
      (value "TMCS1100")
      (footprint "eagle-import:SOIC8_D_TEX")
      (fields
        (field (name "MANUFACTURER_PART_NUMBER") "TMCS1100AxQDR")
        (field (name "COPYRIGHT") "Copyright (C) 2018 Accelerated Designs. All rights reserved")
      )
      (libsource (lib "eagle-import") (part "TMCS1100"))
    )
    (comp (ref "U8")
      (value "BSC030N08NS5ATMA1")
      (footprint "eagle-import:MOSFET_BSC093N04LSGATMA1")
      (fields (field (name "MF") "Infineon Technologies"))
      (libsource (lib "eagle-import") (part "BSC030N08NS5ATMA1"))
    )
    (comp (ref "U9")
      (value "BSC030N08NS5ATMA1")
      (footprint "eagle-import:MOSFET_BSC093N04LSGATMA1")
      (fields (field (name "MF") "Infineon Technologies"))
      (libsource (lib "eagle-import") (part "BSC030N08NS5ATMA1"))
    )
    (comp (ref "U10")
      (value "BSC030N08NS5ATMA1")
      (footprint "eagle-import:MOSFET_BSC093N04LSGATMA1")
      (fields (field (name "MF") "Infineon Technologies"))
      (libsource (lib "eagle-import") (part "BSC030N08NS5ATMA1"))
    )
    (comp (ref "U11")
      (value "BSC030N08NS5ATMA1")
      (footprint "eagle-import:MOSFET_BSC093N04LSGATMA1")
      (fields (field (name "MF") "Infineon Technologies"))
      (libsource (lib "eagle-import") (part "BSC030N08NS5ATMA1"))
    )
    (comp (ref "U12")
      (value "BSC030N08NS5ATMA1")
      (footprint "eagle-import:MOSFET_BSC093N04LSGATMA1")
      (fields (field (name "MF") "Infineon Technologies"))
      (libsource (lib "eagle-import") (part "BSC030N08NS5ATMA1"))
    )
    (comp (ref "U13")
      (value "BSC030N08NS5ATMA1")
      (footprint "eagle-import:MOSFET_BSC093N04LSGATMA1")
      (fields (field (name "MF") "Infineon Technologies"))
      (libsource (lib "eagle-import") (part "BSC030N08NS5ATMA1"))
    )
    (comp (ref "U14")
      (value "MCP14XX")
      (footprint "eagle-import:SOT23-5L")
      (libsource (lib "eagle-import") (part "MCP14XX"))
    )
    (comp (ref "U15")
      (value "BSC030N08NS5ATMA1")
      (footprint "eagle-import:MOSFET_BSC093N04LSGATMA1")
      (fields (field (name "MF") "Infineon Technologies"))
      (libsource (lib "eagle-import") (part "BSC030N08NS5ATMA1"))
    )
    (comp (ref "U16")
      (value "BSC030N08NS5ATMA1")
      (footprint "eagle-import:MOSFET_BSC093N04LSGATMA1")
      (fields (field (name "MF") "Infineon Technologies"))
      (libsource (lib "eagle-import") (part "BSC030N08NS5ATMA1"))
    )
    (comp (ref "U17")
      (value "BSC030N08NS5ATMA1")
      (footprint "eagle-import:MOSFET_BSC093N04LSGATMA1")
      (fields (field (name "MF") "Infineon Technologies"))
      (libsource (lib "eagle-import") (part "BSC030N08NS5ATMA1"))
    )
    (comp (ref "Y1")
      (value "25MHz")
      (footprint "eagle-import:ECS-327KE-TR")
      (fields
        (field (name "DIGIKEY_PART_NUMBER") "XC1751TR-ND")
        (field (name "MANUFACTURER") "ECS Inc.")
        (field (name "MPN") "ECS-327KE-TR")
        (field (name "CREATED_BY") "PCBLayout.com")
      )
      (libsource (lib "eagle-import") (part "ECS-327KE-TR"))
    )
  )
  (nets
    (net (code "1") (name "+3V3") (class "Default")
      (node (ref "C15") (pin "1") (pinfunction "1_1") (pintype "passive"))
      (node (ref "C16") (pin "1") (pinfunction "1_1") (pintype "passive"))
      (node (ref "C17") (pin "1") (pinfunction "1_1") (pintype "passive"))
      (node (ref "C18") (pin "1") (pinfunction "1_1") (pintype "passive"))
      (node (ref "C34") (pin "1") (pinfunction "1_1") (pintype "passive"))
      (node (ref "JP6") (pin "4") (pinfunction "4_4") (pintype "passive"))
      (node (ref "R2") (pin "2") (pinfunction "2_2") (pintype "passive"))
      (node (ref "R29") (pin "2") (pinfunction "2_2") (pintype "passive"))
      (node (ref "R32") (pin "2") (pinfunction "2_2") (pintype "passive"))
      (node (ref "SJ6") (pin "2") (pinfunction "2_2") (pintype "passive"))
      (node (ref "U1") (pin "13") (pinfunction "VCCIO2_13") (pintype "power_in"))
      (node (ref "U1") (pin "2") (pinfunction "VCCIO1_2") (pintype "power_in"))
      (node (ref "U1") (pin "43") (pinfunction "VCCIO3_43") (pintype "power_in"))
      (node (ref "U1") (pin "52") (pinfunction "VCCIO4_52") (pintype "power_in"))
      (node (ref "U1") (pin "61") (pinfunction "VCCIO5_61") (pintype "power_in"))
      (node (ref "U1") (pin "72") (pinfunction "VCCIO6_72") (pintype "power_in"))
      (node (ref "U19") (pin "14") (pinfunction "VCC_14") (pintype "bidirectional"))
      (node (ref "U21") (pin "2") (pinfunction "OUT_2") (pintype "output"))
      (node (ref "U21") (pin "4") (pinfunction "OUT_4") (pintype "output"))
      (node (ref "Y1") (pin "4") (pinfunction "VDD_4") (pintype "power_in"))
    )
    (net (code "2") (name "+5V") (class "Default")
      (node (ref "C32") (pin "1") (pinfunction "1_1") (pintype "passive"))
      (node (ref "C38") (pin "1") (pinfunction "1_1") (pintype "passive"))
      (node (ref "JP11") (pin "1") (pinfunction "1_1") (pintype "passive"))
      (node (ref "JP12") (pin "1") (pinfunction "1_1") (pintype "passive"))
      (node (ref "JP2") (pin "2") (pinfunction "2_2") (pintype "passive"))
      (node (ref "JP4") (pin "2") (pinfunction "2_2") (pintype "passive"))
      (node (ref "JP5") (pin "1") (pinfunction "1_1") (pintype "passive"))
      (node (ref "L1") (pin "2") (pinfunction "2_2") (pintype "passive"))
      (node (ref "L2") (pin "1") (pinfunction "1_1") (pintype "passive"))
      (node (ref "R1") (pin "2") (pinfunction "2_2") (pintype "passive"))
      (node (ref "R34") (pin "2") (pinfunction "2_2") (pintype "passive"))
      (node (ref "R35") (pin "2") (pinfunction "2_2") (pintype "passive"))
      (node (ref "R36") (pin "2") (pinfunction "2_2") (pintype "passive"))
      (node (ref "R37") (pin "2") (pinfunction "2_2") (pintype "passive"))
      (node (ref "R38") (pin "2") (pinfunction "2_2") (pintype "passive"))
      (node (ref "R39") (pin "2") (pinfunction "2_2") (pintype "passive"))
      (node (ref "U21") (pin "3") (pinfunction "IN_3") (pintype "input"))
      (node (ref "U24") (pin "4") (pinfunction "NSHDN_4") (pintype "bidirectional"))
      (node (ref "U24") (pin "5") (pinfunction "VIN_5") (pintype "bidirectional"))
    )
    (net (code "3") (name "2.5V_REF") (class "Default")
      (node (ref "C26") (pin "1") (pinfunction "1_1") (pintype "passive"))
      (node (ref "JP3") (pin "2") (pinfunction "2_2") (pintype "passive"))
      (node (ref "JP3") (pin "4") (pinfunction "4_4") (pintype "passive"))
      (node (ref "JP3") (pin "6") (pinfunction "6_6") (pintype "passive"))
      (node (ref "R30") (pin "2") (pinfunction "2_2") (pintype "passive"))
      (node (ref "SJ1") (pin "1") (pinfunction "1_1") (pintype "passive"))
      (node (ref "SJ2") (pin "1") (pinfunction "1_1") (pintype "passive"))
      (node (ref "U18") (pin "6") (pinfunction "INB-_6") (pintype "bidirectional"))
      (node (ref "U18") (pin "7") (pinfunction "OUTB_7") (pintype "bidirectional"))
    )
    (net (code "4") (name "2.5V_REF_A") (class "Default")
      (node (ref "JP14") (pin "2") (pinfunction "2_2") (pintype "passive"))
      (node (ref "SJ1") (pin "2") (pinfunction "2_2") (pintype "passive"))
      (node (ref "U1") (pin "17") (pinfunction "ADC_I0_NEG_17") (pintype "input"))
    )
    (net (code "5") (name "2.5V_REF_C") (class "Default")
      (node (ref "JP13") (pin "2") (pinfunction "2_2") (pintype "passive"))
      (node (ref "SJ2") (pin "2") (pinfunction "2_2") (pintype "passive"))
      (node (ref "U1") (pin "19") (pinfunction "ADC_I1_NEG_19") (pintype "input"))
    )
    (net (code "6") (name "2.5V_REF_RAW") (class "Default")
      (node (ref "R17") (pin "1") (pinfunction "1_1") (pintype "passive"))
      (node (ref "R18") (pin "2") (pinfunction "2_2") (pintype "passive"))
      (node (ref "U18") (pin "5") (pinfunction "INB+_5") (pintype "bidirectional"))
    )
    (net (code "7") (name "5V_SENSE") (class "Default")
      (node (ref "C2") (pin "2") (pinfunction "2_2") (pintype "passive"))
      (node (ref "C23") (pin "2") (pinfunction "2_2") (pintype "passive"))
      (node (ref "C24") (pin "1") (pinfunction "1_1") (pintype "passive"))
      (node (ref "C25") (pin "1") (pinfunction "1_1") (pintype "passive"))
      (node (ref "R17") (pin "2") (pinfunction "2_2") (pintype "passive"))
      (node (ref "U1") (pin "23") (pinfunction "V5_23") (pintype "power_in"))
      (node (ref "U18") (pin "4") (pinfunction "VCC_4") (pintype "bidirectional"))
      (node (ref "U25") (pin "2") (pinfunction "OUT_2") (pintype "output"))
      (node (ref "U25") (pin "4") (pinfunction "OUT_4") (pintype "output"))
      (node (ref "U6") (pin "8") (pinfunction "VS_8") (pintype "power_in"))
      (node (ref "U7") (pin "8") (pinfunction "VS_8") (pintype "power_in"))
    )
    (net (code "8") (name "AENC_UX") (class "Default")
      (node (ref "JP2") (pin "6") (pinfunction "6_6") (pintype "passive"))
      (node (ref "U1") (pin "25") (pinfunction "AENC_UX_POS_25") (pintype "input"))
    )
    (net (code "9") (name "AENC_UX_N") (class "Default")
      (node (ref "JP2") (pin "5") (pinfunction "5_5") (pintype "passive"))
      (node (ref "JP3") (pin "3") (pinfunction "3_3") (pintype "passive"))
      (node (ref "U1") (pin "26") (pinfunction "AENC_UX_NEG_26") (pintype "input"))
    )
    (net (code "10") (name "AENC_VN") (class "Default")
      (node (ref "JP2") (pin "8") (pinfunction "8_8") (pintype "passive"))
      (node (ref "U1") (pin "27") (pinfunction "AENC_VN_POS_27") (pintype "input"))
    )
    (net (code "11") (name "AENC_VN_N") (class "Default")
      (node (ref "JP2") (pin "7") (pinfunction "7_7") (pintype "passive"))
      (node (ref "JP3") (pin "1") (pinfunction "1_1") (pintype "passive"))
      (node (ref "U1") (pin "28") (pinfunction "AENC_VN_NEG_28") (pintype "input"))
    )
    (net (code "12") (name "AENC_WY") (class "Default")
      (node (ref "JP2") (pin "4") (pinfunction "4_4") (pintype "passive"))
      (node (ref "U1") (pin "29") (pinfunction "AENC_WY_POS_29") (pintype "input"))
    )
    (net (code "13") (name "AENC_WY_N") (class "Default")
      (node (ref "JP2") (pin "3") (pinfunction "3_3") (pintype "passive"))
      (node (ref "JP3") (pin "5") (pinfunction "5_5") (pintype "passive"))
      (node (ref "U1") (pin "30") (pinfunction "AENC_WY_NEG_30") (pintype "input"))
    )
    (net (code "14") (name "AGPI_A") (class "Default")
      (node (ref "JP1") (pin "2") (pinfunction "2_2") (pintype "passive"))
      (node (ref "U1") (pin "21") (pinfunction "AGPI_A_21") (pintype "input"))
    )
    (net (code "15") (name "AGPI_B") (class "Default")
      (node (ref "U1") (pin "22") (pinfunction "AGPI_B_22") (pintype "input"))
      (node (ref "U18") (pin "1") (pinfunction "OUTA_1") (pintype "bidirectional"))
      (node (ref "U18") (pin "2") (pinfunction "INA-_2") (pintype "bidirectional"))
    )
    (net (code "16") (name "BRAKE_CTRL") (class "Default")
      (node (ref "D10") (pin "C") (pinfunction "C_C") (pintype "passive"))
      (node (ref "D9") (pin "C") (pinfunction "C_C") (pintype "passive"))
      (node (ref "R15") (pin "2") (pinfunction "2_2") (pintype "passive"))
      (node (ref "R16") (pin "2") (pinfunction "2_2") (pintype "passive"))
      (node (ref "U14") (pin "3") (pinfunction "IN_3") (pintype "bidirectional"))
    )
    (net (code "17") (name "BRAKE_CTRL_EXT") (class "Default")
      (node (ref "R16") (pin "1") (pinfunction "1_1") (pintype "passive"))
      (node (ref "X1") (pin "12") (pinfunction "KL_12") (pintype "passive"))
    )
    (net (code "18") (name "BRAKE_CTRL_TMC") (class "Default")
      (node (ref "D9") (pin "A") (pinfunction "A_A") (pintype "passive"))
      (node (ref "U1") (pin "31") (pinfunction "BRAKE_31") (pintype "output"))
    )
    (net (code "19") (name "BRAKE_GATE") (class "Default")
      (node (ref "R21") (pin "2") (pinfunction "2_2") (pintype "passive"))
      (node (ref "U14") (pin "5") (pinfunction "OUT_5") (pintype "bidirectional"))
      (node (ref "U17") (pin "4") (pinfunction "G_4") (pintype "passive"))
    )
    (net (code "20") (name "BRAKE_RES_COMP") (class "Default")
      (node (ref "D10") (pin "A") (pinfunction "A_A") (pintype "passive"))
      (node (ref "U18") (pin "14") (pinfunction "OUTD_14") (pintype "bidirectional"))
    )
    (net (code "21") (name "BRAKE_RES_TH") (class "Default")
      (node (ref "R32") (pin "1") (pinfunction "1_1") (pintype "passive"))
      (node (ref "R33") (pin "2") (pinfunction "2_2") (pintype "passive"))
      (node (ref "U18") (pin "13") (pinfunction "IND-_13") (pintype "bidirectional"))
    )
    (net (code "22") (name "CLK_25M") (class "Default")
      (node (ref "U1") (pin "51") (pinfunction "CLK_51") (pintype "input"))
      (node (ref "Y1") (pin "3") (pinfunction "OUTPUT_3") (pintype "output"))
    )
    (net (code "23") (name "CS1") (class "Default")
      (node (ref "SJ3") (pin "1") (pinfunction "1_1") (pintype "passive"))
      (node (ref "X1") (pin "7") (pinfunction "KL_7") (pintype "passive"))
    )
    (net (code "24") (name "CS2") (class "Default")
      (node (ref "SJ4") (pin "1") (pinfunction "1_1") (pintype "passive"))
      (node (ref "X1") (pin "9") (pinfunction "KL_9") (pintype "passive"))
    )
    (net (code "25") (name "CS3") (class "Default")
      (node (ref "SJ5") (pin "1") (pinfunction "1_1") (pintype "passive"))
      (node (ref "X1") (pin "10") (pinfunction "KL_10") (pintype "passive"))
    )
    (net (code "26") (name "CS_TMC") (class "Default")
      (node (ref "SJ3") (pin "2") (pinfunction "2_2") (pintype "passive"))
      (node (ref "SJ4") (pin "2") (pinfunction "2_2") (pintype "passive"))
      (node (ref "SJ5") (pin "2") (pinfunction "2_2") (pintype "passive"))
      (node (ref "U1") (pin "6") (pinfunction "SPI_NSCS_6") (pintype "input"))
    )
    (net (code "27") (name "C_HS_A") (class "Default")
      (node (ref "U1") (pin "39") (pinfunction "PWM_UX1_H_39") (pintype "output"))
      (node (ref "U5") (pin "2") (pinfunction "HI_2") (pintype "input"))
    )
    (net (code "28") (name "C_HS_B") (class "Default")
      (node (ref "U1") (pin "41") (pinfunction "PWM_VX2_H_41") (pintype "output"))
      (node (ref "U4") (pin "2") (pinfunction "HI_2") (pintype "input"))
    )
    (net (code "29") (name "C_HS_C") (class "Default")
      (node (ref "U1") (pin "46") (pinfunction "PWM_WY1_H_46") (pintype "output"))
      (node (ref "U3") (pin "2") (pinfunction "HI_2") (pintype "input"))
    )
    (net (code "30") (name "C_HS_D") (class "Default")
      (node (ref "U1") (pin "48") (pinfunction "PWM_Y2_H_48") (pintype "output"))
      (node (ref "U2") (pin "2") (pinfunction "HI_2") (pintype "input"))
    )
    (net (code "31") (name "C_LS_A") (class "Default")
      (node (ref "U1") (pin "40") (pinfunction "PWM_UX1_L_40") (pintype "output"))
      (node (ref "U5") (pin "3") (pinfunction "LI_3") (pintype "input"))
    )
    (net (code "32") (name "C_LS_B") (class "Default")
      (node (ref "U1") (pin "42") (pinfunction "PWM_VX2_L_42") (pintype "output"))
      (node (ref "U4") (pin "3") (pinfunction "LI_3") (pintype "input"))
    )
    (net (code "33") (name "C_LS_C") (class "Default")
      (node (ref "U1") (pin "47") (pinfunction "PWM_WY1_L_47") (pintype "output"))
      (node (ref "U3") (pin "3") (pinfunction "LI_3") (pintype "input"))
    )
    (net (code "34") (name "C_LS_D") (class "Default")
      (node (ref "U1") (pin "49") (pinfunction "PWM_Y2_L_49") (pintype "output"))
      (node (ref "U2") (pin "3") (pinfunction "LI_3") (pintype "input"))
    )
    (net (code "35") (name "DIR") (class "Default")
      (node (ref "JP10") (pin "3") (pinfunction "3_3") (pintype "passive"))
      (node (ref "U1") (pin "56") (pinfunction "DIR_56") (pintype "input"))
    )
    (net (code "36") (name "ENABLE") (class "Default")
      (node (ref "JP7") (pin "2") (pinfunction "2_2") (pintype "passive"))
      (node (ref "R22") (pin "1") (pinfunction "1_1") (pintype "passive"))
      (node (ref "U1") (pin "55") (pinfunction "ENI_55") (pintype "input"))
    )
    (net (code "37") (name "ENC2_A") (class "Default")
      (node (ref "JP9") (pin "2") (pinfunction "2_2") (pintype "passive"))
      (node (ref "U1") (pin "64") (pinfunction "ENC2_A_64") (pintype "input"))
    )
    (net (code "38") (name "ENC2_B") (class "Default")
      (node (ref "JP9") (pin "4") (pinfunction "4_4") (pintype "passive"))
      (node (ref "U1") (pin "65") (pinfunction "ENC2_B_65") (pintype "input"))
    )
    (net (code "39") (name "ENC2_Z") (class "Default")
      (node (ref "JP9") (pin "6") (pinfunction "6_6") (pintype "passive"))
      (node (ref "U1") (pin "66") (pinfunction "ENC2_N_66") (pintype "input"))
    )
    (net (code "40") (name "ENC_A") (class "Default")
      (node (ref "U1") (pin "35") (pinfunction "ENC_A_35") (pintype "input"))
      (node (ref "U19") (pin "6") (pinfunction "3Y_6") (pintype "bidirectional"))
    )
    (net (code "41") (name "ENC_A_5V") (class "Default")
      (node (ref "JP11") (pin "4") (pinfunction "4_4") (pintype "passive"))
      (node (ref "R37") (pin "1") (pinfunction "1_1") (pintype "passive"))
      (node (ref "U19") (pin "5") (pinfunction "3A_5") (pintype "bidirectional"))
    )
    (net (code "42") (name "ENC_B") (class "Default")
      (node (ref "U1") (pin "34") (pinfunction "ENC_B_34") (pintype "input"))
      (node (ref "U19") (pin "4") (pinfunction "2Y_4") (pintype "bidirectional"))
    )
    (net (code "43") (name "ENC_B_5V") (class "Default")
      (node (ref "JP11") (pin "3") (pinfunction "3_3") (pintype "passive"))
      (node (ref "R35") (pin "1") (pinfunction "1_1") (pintype "passive"))
      (node (ref "U19") (pin "3") (pinfunction "2A_3") (pintype "bidirectional"))
    )
    (net (code "44") (name "ENC_Z") (class "Default")
      (node (ref "U1") (pin "33") (pinfunction "ENC_N_33") (pintype "input"))
      (node (ref "U19") (pin "2") (pinfunction "1Y_2") (pintype "bidirectional"))
    )
    (net (code "45") (name "ENC_Z_5V") (class "Default")
      (node (ref "JP11") (pin "2") (pinfunction "2_2") (pintype "passive"))
      (node (ref "R34") (pin "1") (pinfunction "1_1") (pintype "passive"))
      (node (ref "U19") (pin "1") (pinfunction "1A_1") (pintype "bidirectional"))
    )
    (net (code "46") (name "ENO") (class "Default")
      (node (ref "JP1") (pin "1") (pinfunction "1_1") (pintype "passive"))
      (node (ref "U1") (pin "32") (pinfunction "ENO_32") (pintype "output"))
    )
    (net (code "47") (name "FLAG") (class "Default")
      (node (ref "D1") (pin "C") (pinfunction "C_C") (pintype "passive"))
      (node (ref "R3") (pin "2") (pinfunction "2_2") (pintype "passive"))
      (node (ref "X1") (pin "11") (pinfunction "KL_11") (pintype "passive"))
    )
    (net (code "48") (name "GND") (class "Default")
      (node (ref "C1") (pin "1") (pinfunction "1_1") (pintype "passive"))
      (node (ref "C15") (pin "2") (pinfunction "2_2") (pintype "passive"))
      (node (ref "C16") (pin "2") (pinfunction "2_2") (pintype "passive"))
      (node (ref "C17") (pin "2") (pinfunction "2_2") (pintype "passive"))
      (node (ref "C18") (pin "2") (pinfunction "2_2") (pintype "passive"))
      (node (ref "C29") (pin "1") (pinfunction "1_1") (pintype "passive"))
      (node (ref "C3") (pin "1") (pinfunction "1_1") (pintype "passive"))
      (node (ref "C30") (pin "1") (pinfunction "1_1") (pintype "passive"))
      (node (ref "C31") (pin "1") (pinfunction "1_1") (pintype "passive"))
      (node (ref "C32") (pin "2") (pinfunction "2_2") (pintype "passive"))
      (node (ref "C34") (pin "2") (pinfunction "2_2") (pintype "passive"))
      (node (ref "C35") (pin "1") (pinfunction "1_1") (pintype "passive"))
      (node (ref "C37") (pin "1") (pinfunction "1_1") (pintype "passive"))
      (node (ref "C38") (pin "2") (pinfunction "2_2") (pintype "passive"))
      (node (ref "C39") (pin "2") (pinfunction "2_2") (pintype "passive"))
      (node (ref "C4") (pin "1") (pinfunction "1_1") (pintype "passive"))
      (node (ref "D14") (pin "A") (pinfunction "A_A") (pintype "passive"))
      (node (ref "D15") (pin "A") (pinfunction "A_A") (pintype "passive"))
      (node (ref "H3") (pin "B3,0") (pinfunction "MOUNT_B3,0") (pintype "passive"))
      (node (ref "H4") (pin "B3,0") (pinfunction "MOUNT_B3,0") (pintype "passive"))
      (node (ref "H5") (pin "B3,0") (pinfunction "MOUNT_B3,0") (pintype "passive"))
      (node (ref "H6") (pin "B3,0") (pinfunction "MOUNT_B3,0") (pintype "passive"))
      (node (ref "JP11") (pin "5") (pinfunction "5_5") (pintype "passive"))
      (node (ref "JP12") (pin "5") (pinfunction "5_5") (pintype "passive"))
      (node (ref "JP2") (pin "1") (pinfunction "1_1") (pintype "passive"))
      (node (ref "JP6") (pin "3") (pinfunction "3_3") (pintype "passive"))
      (node (ref "JP7") (pin "1") (pinfunction "1_1") (pintype "passive"))
      (node (ref "LED1") (pin "C") (pinfunction "C_C") (pintype "passive"))
      (node (ref "R15") (pin "1") (pinfunction "1_1") (pintype "passive"))
      (node (ref "R19") (pin "1") (pinfunction "1_1") (pintype "passive"))
      (node (ref "R26") (pin "1") (pinfunction "1_1") (pintype "passive"))
      (node (ref "R28") (pin "1") (pinfunction "1_1") (pintype "passive"))
      (node (ref "R3") (pin "1") (pinfunction "1_1") (pintype "passive"))
      (node (ref "R33") (pin "1") (pinfunction "1_1") (pintype "passive"))
      (node (ref "R44") (pin "2") (pinfunction "2_2") (pintype "passive"))
      (node (ref "R46") (pin "1") (pinfunction "1_1") (pintype "passive"))
      (node (ref "R47") (pin "2") (pinfunction "2_2") (pintype "passive"))
      (node (ref "R48") (pin "1") (pinfunction "1_1") (pintype "passive"))
      (node (ref "R49") (pin "1") (pinfunction "1_1") (pintype "passive"))
      (node (ref "R52") (pin "1") (pinfunction "1_1") (pintype "passive"))
      (node (ref "U1") (pin "14") (pinfunction "GNDIO2_14") (pintype "power_in"))
      (node (ref "U1") (pin "3") (pinfunction "GNDIO1_3") (pintype "power_in"))
      (node (ref "U1") (pin "44") (pinfunction "GNDIO3_44") (pintype "power_in"))
      (node (ref "U1") (pin "53") (pinfunction "GNDIO4_53") (pintype "power_in"))
      (node (ref "U1") (pin "54") (pinfunction "TEST_54") (pintype "input"))
      (node (ref "U1") (pin "59") (pinfunction "PWM_IDLE_H_59") (pintype "input"))
      (node (ref "U1") (pin "60") (pinfunction "PWM_IDLE_L_60") (pintype "input"))
      (node (ref "U1") (pin "62") (pinfunction "GNDIO5_62") (pintype "power_in"))
      (node (ref "U1") (pin "73") (pinfunction "GNDIO6_73") (pintype "power_in"))
      (node (ref "U1") (pin "77") (pinfunction "GNDIO6_77") (pintype "power_in"))
      (node (ref "U19") (pin "7") (pinfunction "GND_7") (pintype "bidirectional"))
      (node (ref "U21") (pin "1") (pinfunction "ADJ_1") (pintype "input"))
      (node (ref "U23") (pin "3") (pinfunction "SGND_3") (pintype "power_in"))
      (node (ref "U23") (pin "6") (pinfunction "GND_6") (pintype "power_in"))
      (node (ref "U24") (pin "2") (pinfunction "GND_2") (pintype "bidirectional"))
      (node (ref "X1") (pin "1") (pinfunction "KL_1") (pintype "passive"))
      (node (ref "Y1") (pin "2") (pinfunction "GND_2") (pintype "power_in"))
    )
    (net (code "49") (name "GNDA") (class "Default")
      (node (ref "C2") (pin "1") (pinfunction "1_1") (pintype "passive"))
      (node (ref "C23") (pin "1") (pinfunction "1_1") (pintype "passive"))
      (node (ref "C24") (pin "2") (pinfunction "2_2") (pintype "passive"))
      (node (ref "C25") (pin "2") (pinfunction "2_2") (pintype "passive"))
      (node (ref "C26") (pin "2") (pinfunction "2_2") (pintype "passive"))
      (node (ref "C28") (pin "2") (pinfunction "2_2") (pintype "passive"))
      (node (ref "C40") (pin "2") (pinfunction "2_2") (pintype "passive"))
      (node (ref "C41") (pin "2") (pinfunction "2_2") (pintype "passive"))
      (node (ref "C42") (pin "2") (pinfunction "2_2") (pintype "passive"))
      (node (ref "C43") (pin "2") (pinfunction "2_2") (pintype "passive"))
      (node (ref "R18") (pin "1") (pinfunction "1_1") (pintype "passive"))
      (node (ref "R24") (pin "1") (pinfunction "1_1") (pintype "passive"))
      (node (ref "R31") (pin "1") (pinfunction "1_1") (pintype "passive"))
      (node (ref "R47") (pin "1") (pinfunction "1_1") (pintype "passive"))
      (node (ref "U1") (pin "24") (pinfunction "GNDA_24") (pintype "power_in"))
      (node (ref "U18") (pin "11") (pinfunction "GND_11") (pintype "bidirectional"))
      (node (ref "U25") (pin "1") (pinfunction "ADJ_1") (pintype "input"))
      (node (ref "U6") (pin "5") (pinfunction "GND_5") (pintype "passive"))
      (node (ref "U7") (pin "5") (pinfunction "GND_5") (pintype "passive"))
    )
    (net (code "50") (name "GNDI") (class "Default")
      (node (ref "C10") (pin "-") (pinfunction "-_-") (pintype "passive"))
      (node (ref "C11") (pin "2") (pinfunction "2_2") (pintype "passive"))
      (node (ref "C12") (pin "2") (pinfunction "2_2") (pintype "passive"))
      (node (ref "C13") (pin "2") (pinfunction "2_2") (pintype "passive"))
      (node (ref "C14") (pin "2") (pinfunction "2_2") (pintype "passive"))
      (node (ref "C5") (pin "1") (pinfunction "1_1") (pintype "passive"))
      (node (ref "C6") (pin "1") (pinfunction "1_1") (pintype "passive"))
      (node (ref "C7") (pin "1") (pinfunction "1_1") (pintype "passive"))
      (node (ref "C8") (pin "1") (pinfunction "1_1") (pintype "passive"))
      (node (ref "C9") (pin "-") (pinfunction "-_-") (pintype "passive"))
      (node (ref "D13") (pin "A") (pinfunction "A_A") (pintype "passive"))
      (node (ref "R12") (pin "1") (pinfunction "1_1") (pintype "passive"))
      (node (ref "R13") (pin "1") (pinfunction "1_1") (pintype "passive"))
      (node (ref "R14") (pin "1") (pinfunction "1_1") (pintype "passive"))
      (node (ref "R19") (pin "2") (pinfunction "2_2") (pintype "passive"))
      (node (ref "R20") (pin "1") (pinfunction "1_1") (pintype "passive"))
      (node (ref "R21") (pin "1") (pinfunction "1_1") (pintype "passive"))
      (node (ref "R48") (pin "2") (pinfunction "2_2") (pintype "passive"))
      (node (ref "R52") (pin "2") (pinfunction "2_2") (pintype "passive"))
      (node (ref "SJ7") (pin "1") (pinfunction "1_1") (pintype "passive"))
      (node (ref "SJ8") (pin "1") (pinfunction "1_1") (pintype "passive"))
      (node (ref "U11") (pin "1") (pinfunction "S_1") (pintype "passive"))
      (node (ref "U11") (pin "2") (pinfunction "S_2") (pintype "passive"))
      (node (ref "U11") (pin "3") (pinfunction "S_3") (pintype "passive"))
      (node (ref "U13") (pin "1") (pinfunction "S_1") (pintype "passive"))
      (node (ref "U13") (pin "2") (pinfunction "S_2") (pintype "passive"))
      (node (ref "U13") (pin "3") (pinfunction "S_3") (pintype "passive"))
      (node (ref "U14") (pin "1") (pinfunction "GND_1") (pintype "bidirectional"))
      (node (ref "U14") (pin "4") (pinfunction "GND_4") (pintype "bidirectional"))
      (node (ref "U16") (pin "1") (pinfunction "S_1") (pintype "passive"))
      (node (ref "U16") (pin "2") (pinfunction "S_2") (pintype "passive"))
      (node (ref "U16") (pin "3") (pinfunction "S_3") (pintype "passive"))
      (node (ref "U17") (pin "1") (pinfunction "S_1") (pintype "passive"))
      (node (ref "U17") (pin "2") (pinfunction "S_2") (pintype "passive"))
      (node (ref "U17") (pin "3") (pinfunction "S_3") (pintype "passive"))
      (node (ref "U2") (pin "4") (pinfunction "VSS_4") (pintype "power_in"))
      (node (ref "U2") (pin "9") (pinfunction "EP_9") (pintype "power_in"))
      (node (ref "U20") (pin "2") (pinfunction "GND_2") (pintype "bidirectional"))
      (node (ref "U3") (pin "4") (pinfunction "VSS_4") (pintype "power_in"))
      (node (ref "U3") (pin "9") (pinfunction "EP_9") (pintype "power_in"))
      (node (ref "U4") (pin "4") (pinfunction "VSS_4") (pintype "power_in"))
      (node (ref "U4") (pin "9") (pinfunction "EP_9") (pintype "power_in"))
      (node (ref "U5") (pin "4") (pinfunction "VSS_4") (pintype "power_in"))
      (node (ref "U5") (pin "9") (pinfunction "EP_9") (pintype "power_in"))
      (node (ref "U9") (pin "1") (pinfunction "S_1") (pintype "passive"))
      (node (ref "U9") (pin "2") (pinfunction "S_2") (pintype "passive"))
      (node (ref "U9") (pin "3") (pinfunction "S_3") (pintype "passive"))
      (node (ref "X2") (pin "1") (pinfunction "1_1") (pintype "passive"))
    )
    (net (code "51") (name "GPIO0") (class "Default")
      (node (ref "JP8") (pin "1") (pinfunction "1_1") (pintype "passive"))
      (node (ref "U1") (pin "70") (pinfunction "GPIO0/ADC_I0_MCD_70") (pintype "bidirectional"))
    )
    (net (code "52") (name "GPIO1") (class "Default")
      (node (ref "JP8") (pin "2") (pinfunction "2_2") (pintype "passive"))
      (node (ref "U1") (pin "71") (pinfunction "GPIO1/ADC_I1_MCD_71") (pintype "bidirectional"))
    )
    (net (code "53") (name "GPIO2") (class "Default")
      (node (ref "JP8") (pin "3") (pinfunction "3_3") (pintype "passive"))
      (node (ref "U1") (pin "74") (pinfunction "GPIO2/ADC_VM_MCD_74") (pintype "bidirectional"))
    )
    (net (code "54") (name "GPIO3") (class "Default")
      (node (ref "JP8") (pin "4") (pinfunction "4_4") (pintype "passive"))
      (node (ref "U1") (pin "75") (pinfunction "GPIO3/AGPI_A_MCD/DBGSPI_NSCS_75") (pintype "bidirectional"))
    )
    (net (code "55") (name "GPIO4") (class "Default")
      (node (ref "JP8") (pin "5") (pinfunction "5_5") (pintype "passive"))
      (node (ref "U1") (pin "76") (pinfunction "GPIO4/AGPI_B_MCD/DBGSPI_SCK_76") (pintype "bidirectional"))
    )
    (net (code "56") (name "GPIO5") (class "Default")
      (node (ref "JP8") (pin "6") (pinfunction "6_6") (pintype "passive"))
      (node (ref "U1") (pin "1") (pinfunction "GPIO5/AENC_UX_MCD/DBGSPI_MOSI_1") (pintype "bidirectional"))
    )
    (net (code "57") (name "GPIO6") (class "Default")
      (node (ref "JP8") (pin "7") (pinfunction "7_7") (pintype "passive"))
      (node (ref "U1") (pin "4") (pinfunction "GPIO6/AENC_VN_MCD/DBGSPI_MISO_4") (pintype "bidirectional"))
    )
    (net (code "58") (name "GPIO7") (class "Default")
      (node (ref "JP8") (pin "8") (pinfunction "8_8") (pintype "passive"))
      (node (ref "U1") (pin "5") (pinfunction "GPIO7/AENC_WY_MCD/DBGSPI_TRG_5") (pintype "bidirectional"))
    )
    (net (code "59") (name "G_HS_A") (class "Default")
      (node (ref "D22") (pin "A") (pinfunction "A_A") (pintype "passive"))
      (node (ref "D6") (pin "C") (pinfunction "C_C") (pintype "passive"))
      (node (ref "R10") (pin "1") (pinfunction "1_1") (pintype "passive"))
      (node (ref "U8") (pin "4") (pinfunction "G_4") (pintype "passive"))
    )
    (net (code "60") (name "G_HS_B") (class "Default")
      (node (ref "D21") (pin "A") (pinfunction "A_A") (pintype "passive"))
      (node (ref "D7") (pin "C") (pinfunction "C_C") (pintype "passive"))
      (node (ref "R8") (pin "1") (pinfunction "1_1") (pintype "passive"))
      (node (ref "U10") (pin "4") (pinfunction "G_4") (pintype "passive"))
    )
    (net (code "61") (name "G_HS_C") (class "Default")
      (node (ref "D23") (pin "A") (pinfunction "A_A") (pintype "passive"))
      (node (ref "D8") (pin "C") (pinfunction "C_C") (pintype "passive"))
      (node (ref "R6") (pin "1") (pinfunction "1_1") (pintype "passive"))
      (node (ref "U12") (pin "4") (pinfunction "G_4") (pintype "passive"))
    )
    (net (code "62") (name "G_HS_D") (class "Default")
      (node (ref "D11") (pin "C") (pinfunction "C_C") (pintype "passive"))
      (node (ref "D24") (pin "A") (pinfunction "A_A") (pintype "passive"))
      (node (ref "R4") (pin "1") (pinfunction "1_1") (pintype "passive"))
      (node (ref "U15") (pin "4") (pinfunction "G_4") (pintype "passive"))
    )
    (net (code "63") (name "G_LS_A") (class "Default")
      (node (ref "D17") (pin "A") (pinfunction "A_A") (pintype "passive"))
      (node (ref "R11") (pin "1") (pinfunction "1_1") (pintype "passive"))
      (node (ref "R12") (pin "2") (pinfunction "2_2") (pintype "passive"))
      (node (ref "U9") (pin "4") (pinfunction "G_4") (pintype "passive"))
    )
    (net (code "64") (name "G_LS_B") (class "Default")
      (node (ref "D18") (pin "A") (pinfunction "A_A") (pintype "passive"))
      (node (ref "R13") (pin "2") (pinfunction "2_2") (pintype "passive"))
      (node (ref "R9") (pin "1") (pinfunction "1_1") (pintype "passive"))
      (node (ref "U11") (pin "4") (pinfunction "G_4") (pintype "passive"))
    )
    (net (code "65") (name "G_LS_C") (class "Default")
      (node (ref "D19") (pin "A") (pinfunction "A_A") (pintype "passive"))
      (node (ref "R14") (pin "2") (pinfunction "2_2") (pintype "passive"))
      (node (ref "R7") (pin "1") (pinfunction "1_1") (pintype "passive"))
      (node (ref "U13") (pin "4") (pinfunction "G_4") (pintype "passive"))
    )
    (net (code "66") (name "G_LS_D") (class "Default")
      (node (ref "D20") (pin "A") (pinfunction "A_A") (pintype "passive"))
      (node (ref "R20") (pin "2") (pinfunction "2_2") (pintype "passive"))
      (node (ref "R5") (pin "1") (pinfunction "1_1") (pintype "passive"))
      (node (ref "U16") (pin "4") (pinfunction "G_4") (pintype "passive"))
    )
    (net (code "67") (name "HALL_UX") (class "Default")
      (node (ref "U1") (pin "38") (pinfunction "HALL_UX_38") (pintype "input"))
      (node (ref "U19") (pin "12") (pinfunction "6Y_12") (pintype "bidirectional"))
    )
    (net (code "68") (name "HALL_UX_5V") (class "Default")
      (node (ref "C29") (pin "2") (pinfunction "2_2") (pintype "passive"))
      (node (ref "R40") (pin "1") (pinfunction "1_1") (pintype "passive"))
      (node (ref "U19") (pin "13") (pinfunction "6A_13") (pintype "bidirectional"))
    )
    (net (code "69") (name "HALL_V") (class "Default")
      (node (ref "U1") (pin "37") (pinfunction "HALL_V_37") (pintype "input"))
      (node (ref "U19") (pin "10") (pinfunction "5Y_10") (pintype "bidirectional"))
    )
    (net (code "70") (name "HALL_V_5V") (class "Default")
      (node (ref "C30") (pin "2") (pinfunction "2_2") (pintype "passive"))
      (node (ref "R41") (pin "1") (pinfunction "1_1") (pintype "passive"))
      (node (ref "U19") (pin "11") (pinfunction "5A_11") (pintype "bidirectional"))
    )
    (net (code "71") (name "HALL_WY") (class "Default")
      (node (ref "U1") (pin "36") (pinfunction "HALL_WY_36") (pintype "input"))
      (node (ref "U19") (pin "8") (pinfunction "4Y_8") (pintype "bidirectional"))
    )
    (net (code "72") (name "HALL_WY_5V") (class "Default")
      (node (ref "C31") (pin "2") (pinfunction "2_2") (pintype "passive"))
      (node (ref "R42") (pin "1") (pinfunction "1_1") (pintype "passive"))
      (node (ref "U19") (pin "9") (pinfunction "4A_9") (pintype "bidirectional"))
    )
    (net (code "73") (name "INPUT_GATE") (class "Default")
      (node (ref "U20") (pin "5") (pinfunction "GATE_5") (pintype "bidirectional"))
      (node (ref "U22") (pin "4") (pinfunction "G_4") (pintype "passive"))
    )
    (net (code "74") (name "MISO") (class "Default")
      (node (ref "U1") (pin "9") (pinfunction "SPI_MISO_9") (pintype "output"))
      (node (ref "X1") (pin "6") (pinfunction "KL_6") (pintype "passive"))
    )
    (net (code "75") (name "MOSI") (class "Default")
      (node (ref "U1") (pin "8") (pinfunction "SPI_MOSI_8") (pintype "input"))
      (node (ref "X1") (pin "5") (pinfunction "KL_5") (pintype "passive"))
    )
    (net (code "76") (name "MOT_A") (class "Default")
      (node (ref "C22") (pin "2") (pinfunction "2_2") (pintype "passive"))
      (node (ref "D6") (pin "A") (pinfunction "A_A") (pintype "passive"))
      (node (ref "U5") (pin "6") (pinfunction "HS_6") (pintype "input"))
      (node (ref "U6") (pin "1") (pinfunction "IN+_2_1") (pintype "input"))
      (node (ref "U6") (pin "2") (pinfunction "IN+_2") (pintype "input"))
      (node (ref "U8") (pin "1") (pinfunction "S_1") (pintype "passive"))
      (node (ref "U8") (pin "2") (pinfunction "S_2") (pintype "passive"))
      (node (ref "U8") (pin "3") (pinfunction "S_3") (pintype "passive"))
      (node (ref "U9") (pin "5") (pinfunction "D_5") (pintype "passive"))
    )
    (net (code "77") (name "MOT_A_OUT") (class "Default")
      (node (ref "U6") (pin "3") (pinfunction "IN-_2_3") (pintype "input"))
      (node (ref "U6") (pin "4") (pinfunction "IN-_4") (pintype "input"))
      (node (ref "X3") (pin "1") (pinfunction "1_1") (pintype "passive"))
    )
    (net (code "78") (name "MOT_B") (class "Default")
      (node (ref "C21") (pin "2") (pinfunction "2_2") (pintype "passive"))
      (node (ref "D7") (pin "A") (pinfunction "A_A") (pintype "passive"))
      (node (ref "U10") (pin "1") (pinfunction "S_1") (pintype "passive"))
      (node (ref "U10") (pin "2") (pinfunction "S_2") (pintype "passive"))
      (node (ref "U10") (pin "3") (pinfunction "S_3") (pintype "passive"))
      (node (ref "U11") (pin "5") (pinfunction "D_5") (pintype "passive"))
      (node (ref "U4") (pin "6") (pinfunction "HS_6") (pintype "input"))
      (node (ref "X3") (pin "2") (pinfunction "1_2") (pintype "passive"))
    )
    (net (code "79") (name "MOT_C") (class "Default")
      (node (ref "C20") (pin "2") (pinfunction "2_2") (pintype "passive"))
      (node (ref "D8") (pin "A") (pinfunction "A_A") (pintype "passive"))
      (node (ref "U12") (pin "1") (pinfunction "S_1") (pintype "passive"))
      (node (ref "U12") (pin "2") (pinfunction "S_2") (pintype "passive"))
      (node (ref "U12") (pin "3") (pinfunction "S_3") (pintype "passive"))
      (node (ref "U13") (pin "5") (pinfunction "D_5") (pintype "passive"))
      (node (ref "U3") (pin "6") (pinfunction "HS_6") (pintype "input"))
      (node (ref "U7") (pin "1") (pinfunction "IN+_2_1") (pintype "input"))
      (node (ref "U7") (pin "2") (pinfunction "IN+_2") (pintype "input"))
    )
    (net (code "80") (name "MOT_C_OUT") (class "Default")
      (node (ref "U7") (pin "3") (pinfunction "IN-_2_3") (pintype "input"))
      (node (ref "U7") (pin "4") (pinfunction "IN-_4") (pintype "input"))
      (node (ref "X3") (pin "3") (pinfunction "1_3") (pintype "passive"))
    )
    (net (code "81") (name "MOT_D") (class "Default")
      (node (ref "C19") (pin "2") (pinfunction "2_2") (pintype "passive"))
      (node (ref "D11") (pin "A") (pinfunction "A_A") (pintype "passive"))
      (node (ref "U15") (pin "1") (pinfunction "S_1") (pintype "passive"))
      (node (ref "U15") (pin "2") (pinfunction "S_2") (pintype "passive"))
      (node (ref "U15") (pin "3") (pinfunction "S_3") (pintype "passive"))
      (node (ref "U16") (pin "5") (pinfunction "D_5") (pintype "passive"))
      (node (ref "U2") (pin "6") (pinfunction "HS_6") (pintype "input"))
      (node (ref "X3") (pin "4") (pinfunction "1_4") (pintype "passive"))
    )
    (net (code "82") (name "Net-(H1-MOUNT)") (class "Default")
      (node (ref "H1") (pin "B3,0") (pinfunction "MOUNT_B3,0") (pintype "passive"))
      (node (ref "SJ7") (pin "2") (pinfunction "2_2") (pintype "passive"))
    )
    (net (code "83") (name "Net-(H2-MOUNT)") (class "Default")
      (node (ref "H2") (pin "B3,0") (pinfunction "MOUNT_B3,0") (pintype "passive"))
      (node (ref "SJ8") (pin "2") (pinfunction "2_2") (pintype "passive"))
    )
    (net (code "84") (name "Net-(JP12-Pad2)") (class "Default")
      (node (ref "JP12") (pin "2") (pinfunction "2_2") (pintype "passive"))
      (node (ref "R39") (pin "1") (pinfunction "1_1") (pintype "passive"))
      (node (ref "R42") (pin "2") (pinfunction "2_2") (pintype "passive"))
    )
    (net (code "85") (name "Net-(JP12-Pad3)") (class "Default")
      (node (ref "JP12") (pin "3") (pinfunction "3_3") (pintype "passive"))
      (node (ref "R38") (pin "1") (pinfunction "1_1") (pintype "passive"))
      (node (ref "R41") (pin "2") (pinfunction "2_2") (pintype "passive"))
    )
    (net (code "86") (name "Net-(JP12-Pad4)") (class "Default")
      (node (ref "JP12") (pin "4") (pinfunction "4_4") (pintype "passive"))
      (node (ref "R36") (pin "1") (pinfunction "1_1") (pintype "passive"))
      (node (ref "R40") (pin "2") (pinfunction "2_2") (pintype "passive"))
    )
    (net (code "87") (name "Net-(LED1-PadA)") (class "Default")
      (node (ref "LED1") (pin "A") (pinfunction "A_A") (pintype "passive"))
      (node (ref "R29") (pin "1") (pinfunction "1_1") (pintype "passive"))
    )
    (net (code "88") (name "Net-(U1B-STATUS)") (class "Default")
      (node (ref "D1") (pin "A") (pinfunction "A_A") (pintype "passive"))
      (node (ref "U1") (pin "12") (pinfunction "STATUS_12") (pintype "output"))
    )
    (net (code "89") (name "Net-(U1B-VCCCORE1)") (class "Default")
      (node (ref "C1") (pin "2") (pinfunction "2_2") (pintype "passive"))
      (node (ref "C3") (pin "2") (pinfunction "2_2") (pintype "passive"))
      (node (ref "C4") (pin "2") (pinfunction "2_2") (pintype "passive"))
      (node (ref "U1") (pin "15") (pinfunction "VCCCORE1_15") (pintype "power_in"))
      (node (ref "U1") (pin "45") (pinfunction "VCCCORE2_45") (pintype "power_in"))
      (node (ref "U1") (pin "63") (pinfunction "VCCCORE3_63") (pintype "power_in"))
    )
    (net (code "90") (name "Net-(U2-HB)") (class "Default")
      (node (ref "C19") (pin "1") (pinfunction "1_1") (pintype "passive"))
      (node (ref "D2") (pin "C") (pinfunction "C_C") (pintype "passive"))
      (node (ref "U2") (pin "8") (pinfunction "HB_8") (pintype "input"))
    )
    (net (code "91") (name "Net-(U2-HO)") (class "Default")
      (node (ref "D24") (pin "C") (pinfunction "C_C") (pintype "passive"))
      (node (ref "R4") (pin "2") (pinfunction "2_2") (pintype "passive"))
      (node (ref "U2") (pin "7") (pinfunction "HO_7") (pintype "output"))
    )
    (net (code "92") (name "Net-(U2-LO)") (class "Default")
      (node (ref "D20") (pin "C") (pinfunction "C_C") (pintype "passive"))
      (node (ref "R5") (pin "2") (pinfunction "2_2") (pintype "passive"))
      (node (ref "U2") (pin "5") (pinfunction "LO_5") (pintype "output"))
    )
    (net (code "93") (name "Net-(U3-HB)") (class "Default")
      (node (ref "C20") (pin "1") (pinfunction "1_1") (pintype "passive"))
      (node (ref "D3") (pin "C") (pinfunction "C_C") (pintype "passive"))
      (node (ref "U3") (pin "8") (pinfunction "HB_8") (pintype "input"))
    )
    (net (code "94") (name "Net-(U3-HO)") (class "Default")
      (node (ref "D23") (pin "C") (pinfunction "C_C") (pintype "passive"))
      (node (ref "R6") (pin "2") (pinfunction "2_2") (pintype "passive"))
      (node (ref "U3") (pin "7") (pinfunction "HO_7") (pintype "output"))
    )
    (net (code "95") (name "Net-(U3-LO)") (class "Default")
      (node (ref "D19") (pin "C") (pinfunction "C_C") (pintype "passive"))
      (node (ref "R7") (pin "2") (pinfunction "2_2") (pintype "passive"))
      (node (ref "U3") (pin "5") (pinfunction "LO_5") (pintype "output"))
    )
    (net (code "96") (name "Net-(U4-HB)") (class "Default")
      (node (ref "C21") (pin "1") (pinfunction "1_1") (pintype "passive"))
      (node (ref "D4") (pin "C") (pinfunction "C_C") (pintype "passive"))
      (node (ref "U4") (pin "8") (pinfunction "HB_8") (pintype "input"))
    )
    (net (code "97") (name "Net-(U4-HO)") (class "Default")
      (node (ref "D21") (pin "C") (pinfunction "C_C") (pintype "passive"))
      (node (ref "R8") (pin "2") (pinfunction "2_2") (pintype "passive"))
      (node (ref "U4") (pin "7") (pinfunction "HO_7") (pintype "output"))
    )
    (net (code "98") (name "Net-(U4-LO)") (class "Default")
      (node (ref "D18") (pin "C") (pinfunction "C_C") (pintype "passive"))
      (node (ref "R9") (pin "2") (pinfunction "2_2") (pintype "passive"))
      (node (ref "U4") (pin "5") (pinfunction "LO_5") (pintype "output"))
    )
    (net (code "99") (name "Net-(U5-HB)") (class "Default")
      (node (ref "C22") (pin "1") (pinfunction "1_1") (pintype "passive"))
      (node (ref "D5") (pin "C") (pinfunction "C_C") (pintype "passive"))
      (node (ref "U5") (pin "8") (pinfunction "HB_8") (pintype "input"))
    )
    (net (code "100") (name "Net-(U5-HO)") (class "Default")
      (node (ref "D22") (pin "C") (pinfunction "C_C") (pintype "passive"))
      (node (ref "R10") (pin "2") (pinfunction "2_2") (pintype "passive"))
      (node (ref "U5") (pin "7") (pinfunction "HO_7") (pintype "output"))
    )
    (net (code "101") (name "Net-(U5-LO)") (class "Default")
      (node (ref "D17") (pin "C") (pinfunction "C_C") (pintype "passive"))
      (node (ref "R11") (pin "2") (pinfunction "2_2") (pintype "passive"))
      (node (ref "U5") (pin "5") (pinfunction "LO_5") (pintype "output"))
    )
    (net (code "102") (name "Net-(U6-VOUT)") (class "Default")
      (node (ref "R50") (pin "2") (pinfunction "2_2") (pintype "passive"))
      (node (ref "U6") (pin "7") (pinfunction "VOUT_7") (pintype "output"))
    )
    (net (code "103") (name "Net-(U6-VREF)") (class "Default")
      (node (ref "C43") (pin "1") (pinfunction "1_1") (pintype "passive"))
      (node (ref "JP14") (pin "1") (pinfunction "1_1") (pintype "passive"))
      (node (ref "U6") (pin "6") (pinfunction "VREF_6") (pintype "power_in"))
    )
    (net (code "104") (name "Net-(U7-VOUT)") (class "Default")
      (node (ref "R51") (pin "2") (pinfunction "2_2") (pintype "passive"))
      (node (ref "U7") (pin "7") (pinfunction "VOUT_7") (pintype "output"))
    )
    (net (code "105") (name "Net-(U7-VREF)") (class "Default")
      (node (ref "C42") (pin "1") (pinfunction "1_1") (pintype "passive"))
      (node (ref "JP13") (pin "1") (pinfunction "1_1") (pintype "passive"))
      (node (ref "U7") (pin "6") (pinfunction "VREF_6") (pintype "power_in"))
    )
    (net (code "106") (name "Net-(U20-VCAP)") (class "Default")
      (node (ref "C33") (pin "1") (pinfunction "1_1") (pintype "passive"))
      (node (ref "U20") (pin "1") (pinfunction "VCAP_1") (pintype "bidirectional"))
    )
    (net (code "107") (name "Net-(U23-BST)") (class "Default")
      (node (ref "C36") (pin "1") (pinfunction "1_1") (pintype "passive"))
      (node (ref "U23") (pin "1") (pinfunction "BST_1") (pintype "passive"))
    )
    (net (code "108") (name "Net-(U23-FB)") (class "Default")
      (node (ref "R1") (pin "1") (pinfunction "1_1") (pintype "passive"))
      (node (ref "R49") (pin "2") (pinfunction "2_2") (pintype "passive"))
      (node (ref "U23") (pin "4") (pinfunction "FB_4") (pintype "output"))
    )
    (net (code "109") (name "Net-(U23-LX)") (class "Default")
      (node (ref "C36") (pin "2") (pinfunction "2_2") (pintype "passive"))
      (node (ref "D14") (pin "C") (pinfunction "C_C") (pintype "passive"))
      (node (ref "D15") (pin "C") (pinfunction "C_C") (pintype "passive"))
      (node (ref "L1") (pin "1") (pinfunction "1_1") (pintype "passive"))
      (node (ref "U23") (pin "8") (pinfunction "LX_8") (pintype "passive"))
    )
    (net (code "110") (name "Net-(U23-ON{slash}~{OFF})") (class "Default")
      (node (ref "R43") (pin "1") (pinfunction "1_1") (pintype "passive"))
      (node (ref "R44") (pin "1") (pinfunction "1_1") (pintype "passive"))
      (node (ref "U23") (pin "5") (pinfunction "ON/~{OFF}_5") (pintype "input"))
    )
    (net (code "111") (name "Net-(U23-VD)") (class "Default")
      (node (ref "C35") (pin "2") (pinfunction "2_2") (pintype "passive"))
      (node (ref "U23") (pin "2") (pinfunction "VD_2") (pintype "power_in"))
    )
    (net (code "112") (name "Net-(U24-FB)") (class "Default")
      (node (ref "R45") (pin "1") (pinfunction "1_1") (pintype "passive"))
      (node (ref "R46") (pin "2") (pinfunction "2_2") (pintype "passive"))
      (node (ref "U24") (pin "3") (pinfunction "FB_3") (pintype "bidirectional"))
    )
    (net (code "113") (name "Net-(U24-SW)") (class "Default")
      (node (ref "D16") (pin "A") (pinfunction "A_A") (pintype "passive"))
      (node (ref "L2") (pin "2") (pinfunction "2_2") (pintype "passive"))
      (node (ref "U24") (pin "1") (pinfunction "SW_1") (pintype "bidirectional"))
    )
    (net (code "114") (name "Net-(X1H-KL)") (class "Default")
      (node (ref "R22") (pin "2") (pinfunction "2_2") (pintype "passive"))
      (node (ref "X1") (pin "16") (pinfunction "KL_16") (pintype "passive"))
    )
    (net (code "115") (name "Net-(X1I-KL)") (class "Default")
      (node (ref "JP5") (pin "2") (pinfunction "2_2") (pintype "passive"))
      (node (ref "X1") (pin "2") (pinfunction "KL_2") (pintype "passive"))
    )
    (net (code "116") (name "Net-(X1K-KL)") (class "Default")
      (node (ref "SJ6") (pin "1") (pinfunction "1_1") (pintype "passive"))
      (node (ref "X1") (pin "4") (pinfunction "KL_4") (pintype "passive"))
    )
    (net (code "117") (name "PWM_I") (class "Default")
      (node (ref "JP10") (pin "1") (pinfunction "1_1") (pintype "passive"))
      (node (ref "U1") (pin "58") (pinfunction "PWM_I_58") (pintype "input"))
    )
    (net (code "118") (name "REF_H") (class "Default")
      (node (ref "JP9") (pin "3") (pinfunction "3_3") (pintype "passive"))
      (node (ref "U1") (pin "68") (pinfunction "REF_H_68") (pintype "input"))
    )
    (net (code "119") (name "REF_L") (class "Default")
      (node (ref "JP9") (pin "1") (pinfunction "1_1") (pintype "passive"))
      (node (ref "U1") (pin "67") (pinfunction "REF_L_67") (pintype "input"))
    )
    (net (code "120") (name "REF_R") (class "Default")
      (node (ref "JP9") (pin "5") (pinfunction "5_5") (pintype "passive"))
      (node (ref "U1") (pin "69") (pinfunction "REF_R_69") (pintype "input"))
    )
    (net (code "121") (name "RESET") (class "Default")
      (node (ref "R2") (pin "1") (pinfunction "1_1") (pintype "passive"))
      (node (ref "U1") (pin "50") (pinfunction "NRST_50") (pintype "input"))
      (node (ref "X1") (pin "3") (pinfunction "KL_3") (pintype "passive"))
    )
    (net (code "122") (name "RES_FET") (class "Default")
      (node (ref "D12") (pin "A") (pinfunction "A_A") (pintype "passive"))
      (node (ref "D13") (pin "C") (pinfunction "C_C") (pintype "passive"))
      (node (ref "U17") (pin "5") (pinfunction "D_5") (pintype "passive"))
      (node (ref "X2") (pin "4") (pinfunction "1_4") (pintype "passive"))
    )
    (net (code "123") (name "SCK") (class "Default")
      (node (ref "U1") (pin "7") (pinfunction "SPI_SCK_7") (pintype "input"))
      (node (ref "X1") (pin "8") (pinfunction "KL_8") (pintype "passive"))
    )
    (net (code "124") (name "SENSE_A") (class "Default")
      (node (ref "C28") (pin "1") (pinfunction "1_1") (pintype "passive"))
      (node (ref "R50") (pin "1") (pinfunction "1_1") (pintype "passive"))
      (node (ref "U1") (pin "16") (pinfunction "ADC_I0_POS_16") (pintype "input"))
    )
    (net (code "125") (name "SENSE_C") (class "Default")
      (node (ref "C40") (pin "1") (pinfunction "1_1") (pintype "passive"))
      (node (ref "R51") (pin "1") (pinfunction "1_1") (pintype "passive"))
      (node (ref "U1") (pin "18") (pinfunction "ADC_I1_POS_18") (pintype "input"))
    )
    (net (code "126") (name "STEP") (class "Default")
      (node (ref "JP10") (pin "2") (pinfunction "2_2") (pintype "passive"))
      (node (ref "U1") (pin "57") (pinfunction "STP_57") (pintype "input"))
    )
    (net (code "127") (name "TH_FET") (class "Default")
      (node (ref "R30") (pin "1") (pinfunction "1_1") (pintype "passive"))
      (node (ref "R31") (pin "2") (pinfunction "2_2") (pintype "passive"))
      (node (ref "U18") (pin "3") (pinfunction "INA+_3") (pintype "bidirectional"))
    )
    (net (code "128") (name "UART_RX") (class "Default")
      (node (ref "JP6") (pin "1") (pinfunction "1_1") (pintype "passive"))
      (node (ref "U1") (pin "10") (pinfunction "UART_RXD_10") (pintype "input"))
    )
    (net (code "129") (name "UART_TX") (class "Default")
      (node (ref "JP6") (pin "2") (pinfunction "2_2") (pintype "passive"))
      (node (ref "U1") (pin "11") (pinfunction "UART_TXD_11") (pintype "output"))
    )
    (net (code "130") (name "V+") (class "Default")
      (node (ref "C10") (pin "+") (pinfunction "+_+") (pintype "passive"))
      (node (ref "C11") (pin "1") (pinfunction "1_1") (pintype "passive"))
      (node (ref "C12") (pin "1") (pinfunction "1_1") (pintype "passive"))
      (node (ref "C13") (pin "1") (pinfunction "1_1") (pintype "passive"))
      (node (ref "C14") (pin "1") (pinfunction "1_1") (pintype "passive"))
      (node (ref "C37") (pin "2") (pinfunction "2_2") (pintype "passive"))
      (node (ref "C9") (pin "+") (pinfunction "+_+") (pintype "passive"))
      (node (ref "D12") (pin "C") (pinfunction "C_C") (pintype "passive"))
      (node (ref "R23") (pin "2") (pinfunction "2_2") (pintype "passive"))
      (node (ref "R25") (pin "2") (pinfunction "2_2") (pintype "passive"))
      (node (ref "R43") (pin "2") (pinfunction "2_2") (pintype "passive"))
      (node (ref "U10") (pin "5") (pinfunction "D_5") (pintype "passive"))
      (node (ref "U12") (pin "5") (pinfunction "D_5") (pintype "passive"))
      (node (ref "U15") (pin "5") (pinfunction "D_5") (pintype "passive"))
      (node (ref "U20") (pin "4") (pinfunction "CATHODE_4") (pintype "bidirectional"))
      (node (ref "U22") (pin "5") (pinfunction "D_5") (pintype "passive"))
      (node (ref "U23") (pin "7") (pinfunction "VIN_7") (pintype "power_in"))
      (node (ref "U8") (pin "5") (pinfunction "D_5") (pintype "passive"))
      (node (ref "X2") (pin "2") (pinfunction "1_2") (pintype "passive"))
    )
    (net (code "131") (name "V_EXT") (class "Default")
      (node (ref "R27") (pin "1") (pinfunction "1_1") (pintype "passive"))
      (node (ref "R28") (pin "2") (pinfunction "2_2") (pintype "passive"))
      (node (ref "X1") (pin "13") (pinfunction "KL_13") (pintype "passive"))
    )
    (net (code "132") (name "V_GD") (class "Default")
      (node (ref "C39") (pin "1") (pinfunction "1_1") (pintype "passive"))
      (node (ref "C41") (pin "1") (pinfunction "1_1") (pintype "passive"))
      (node (ref "C5") (pin "2") (pinfunction "2_2") (pintype "passive"))
      (node (ref "C6") (pin "2") (pinfunction "2_2") (pintype "passive"))
      (node (ref "C7") (pin "2") (pinfunction "2_2") (pintype "passive"))
      (node (ref "C8") (pin "2") (pinfunction "2_2") (pintype "passive"))
      (node (ref "D16") (pin "C") (pinfunction "C_C") (pintype "passive"))
      (node (ref "D2") (pin "A") (pinfunction "A_A") (pintype "passive"))
      (node (ref "D3") (pin "A") (pinfunction "A_A") (pintype "passive"))
      (node (ref "D4") (pin "A") (pinfunction "A_A") (pintype "passive"))
      (node (ref "D5") (pin "A") (pinfunction "A_A") (pintype "passive"))
      (node (ref "JP4") (pin "1") (pinfunction "1_1") (pintype "passive"))
      (node (ref "R45") (pin "2") (pinfunction "2_2") (pintype "passive"))
      (node (ref "U14") (pin "2") (pinfunction "VDD_2") (pintype "bidirectional"))
      (node (ref "U2") (pin "1") (pinfunction "VDD_1") (pintype "power_in"))
      (node (ref "U25") (pin "3") (pinfunction "IN_3") (pintype "input"))
      (node (ref "U3") (pin "1") (pinfunction "VDD_1") (pintype "power_in"))
      (node (ref "U4") (pin "1") (pinfunction "VDD_1") (pintype "power_in"))
      (node (ref "U5") (pin "1") (pinfunction "VDD_1") (pintype "power_in"))
    )
    (net (code "133") (name "V_INT") (class "Default")
      (node (ref "R25") (pin "1") (pinfunction "1_1") (pintype "passive"))
      (node (ref "R26") (pin "2") (pinfunction "2_2") (pintype "passive"))
      (node (ref "X1") (pin "14") (pinfunction "KL_14") (pintype "passive"))
    )
    (net (code "134") (name "V_INT_TMC") (class "Default")
      (node (ref "U1") (pin "20") (pinfunction "ADC_VM_20") (pintype "input"))
      (node (ref "U18") (pin "12") (pinfunction "IND+_12") (pintype "bidirectional"))
      (node (ref "U18") (pin "8") (pinfunction "OUTC_8") (pintype "bidirectional"))
      (node (ref "U18") (pin "9") (pinfunction "INC-_9") (pintype "bidirectional"))
    )
    (net (code "135") (name "V_INT_TMC_RAW") (class "Default")
      (node (ref "R23") (pin "1") (pinfunction "1_1") (pintype "passive"))
      (node (ref "R24") (pin "2") (pinfunction "2_2") (pintype "passive"))
      (node (ref "U18") (pin "10") (pinfunction "INC+_10") (pintype "bidirectional"))
    )
    (net (code "136") (name "V_MOT_IN") (class "Default")
      (node (ref "C33") (pin "2") (pinfunction "2_2") (pintype "passive"))
      (node (ref "R27") (pin "2") (pinfunction "2_2") (pintype "passive"))
      (node (ref "U20") (pin "3") (pinfunction "EN_3") (pintype "bidirectional"))
      (node (ref "U20") (pin "6") (pinfunction "ANODE_6") (pintype "bidirectional"))
      (node (ref "U22") (pin "1") (pinfunction "S_1") (pintype "passive"))
      (node (ref "U22") (pin "2") (pinfunction "S_2") (pintype "passive"))
      (node (ref "U22") (pin "3") (pinfunction "S_3") (pintype "passive"))
      (node (ref "X2") (pin "3") (pinfunction "1_3") (pintype "passive"))
    )
    (net (code "137") (name "unconnected-(X1G-KL-Pad15)") (class "Default")
      (node (ref "X1") (pin "15") (pinfunction "KL_15") (pintype "passive"))
    )
    (net (code "138") (name "unconnected-(Y1-TRI_STATE-Pad1)") (class "Default")
      (node (ref "Y1") (pin "1") (pinfunction "TRI_STATE_1") (pintype "input"))
    )
  )
)
